# automata.net
KiCad netlist of a schematic drawn in EAGLE
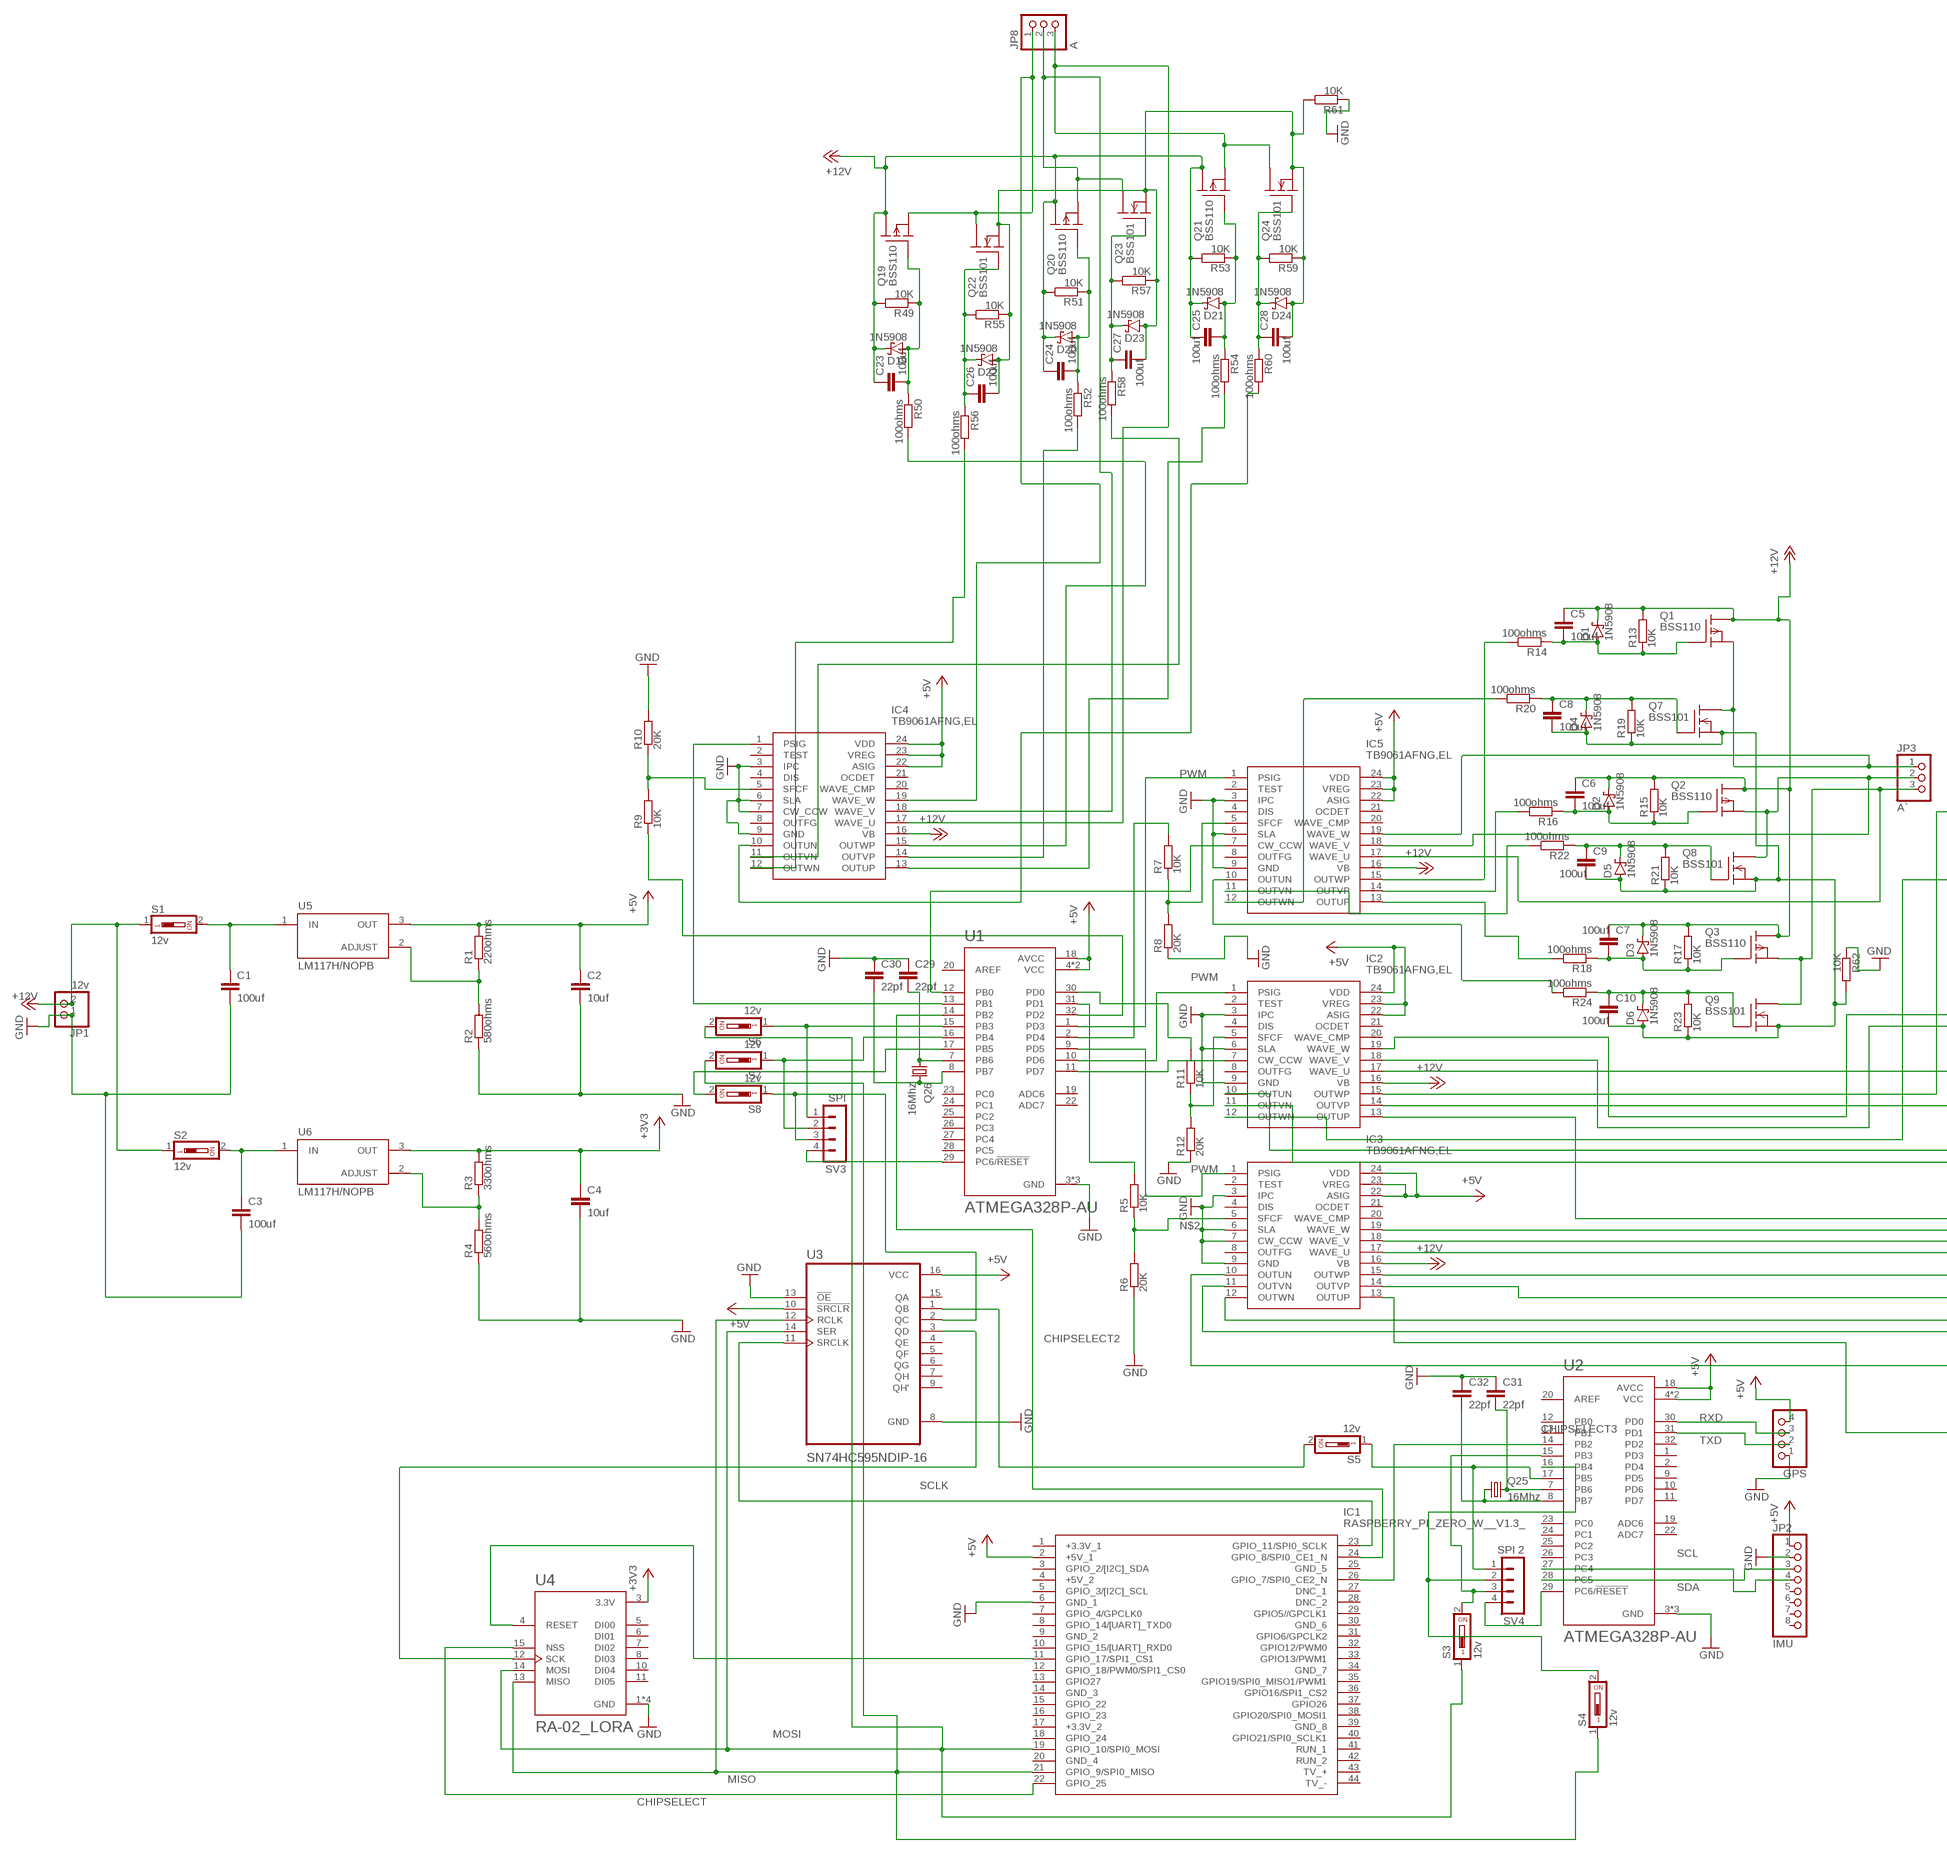
[diagram p0: schematic, sheet 1, part 1 of 2]
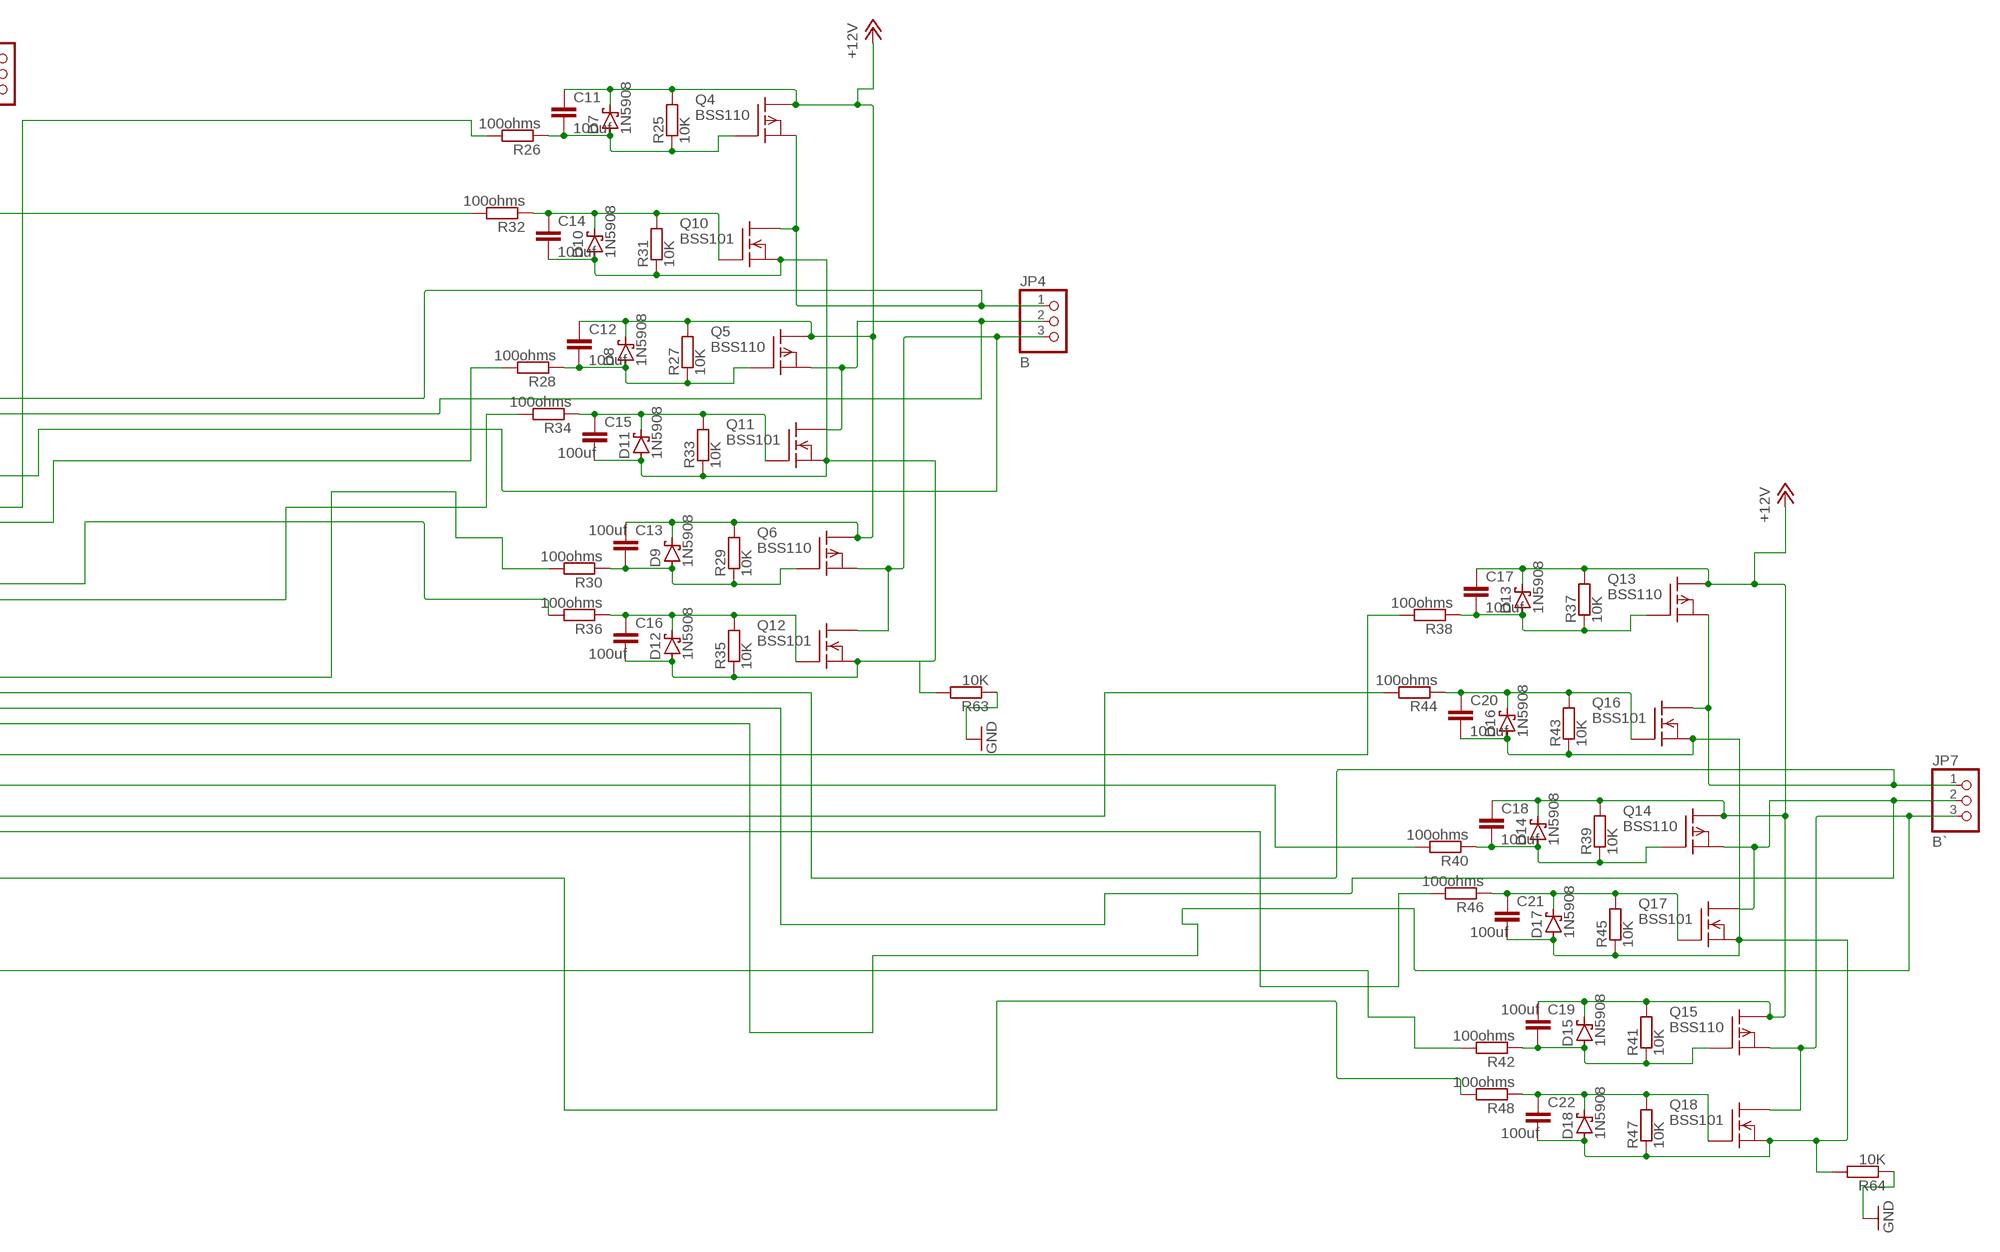
[diagram p1: schematic, sheet 1, part 2 of 2]

(export (version "E")
  (design (tool "Eeschema 10.0.6"))
  (components
    (comp (ref "C1")
      (value "100uf")
      (footprint "eagle-import:C0402K")
      (libsource (lib "eagle-import") (part "C-EUC0402K"))
    )
    (comp (ref "C2")
      (value "10uf")
      (footprint "eagle-import:C0402K")
      (libsource (lib "eagle-import") (part "C-EUC0402K"))
    )
    (comp (ref "C3")
      (value "100uf")
      (footprint "eagle-import:C0402K")
      (libsource (lib "eagle-import") (part "C-EUC0402K"))
    )
    (comp (ref "C4")
      (value "10uf")
      (footprint "eagle-import:C0402K")
      (libsource (lib "eagle-import") (part "C-EUC0402K"))
    )
    (comp (ref "C5")
      (value "100uf")
      (footprint "eagle-import:C0402K")
      (libsource (lib "eagle-import") (part "C-EUC0402K"))
    )
    (comp (ref "C6")
      (value "100uf")
      (footprint "eagle-import:C0402K")
      (libsource (lib "eagle-import") (part "C-EUC0402K"))
    )
    (comp (ref "C7")
      (value "100uf")
      (footprint "eagle-import:C0402K")
      (libsource (lib "eagle-import") (part "C-EUC0402K"))
    )
    (comp (ref "C8")
      (value "100uf")
      (footprint "eagle-import:C0402K")
      (libsource (lib "eagle-import") (part "C-EUC0402K"))
    )
    (comp (ref "C9")
      (value "100uf")
      (footprint "eagle-import:C0402K")
      (libsource (lib "eagle-import") (part "C-EUC0402K"))
    )
    (comp (ref "C10")
      (value "100uf")
      (footprint "eagle-import:C0402K")
      (libsource (lib "eagle-import") (part "C-EUC0402K"))
    )
    (comp (ref "C11")
      (value "100uf")
      (footprint "eagle-import:C0402K")
      (libsource (lib "eagle-import") (part "C-EUC0402K"))
    )
    (comp (ref "C12")
      (value "100uf")
      (footprint "eagle-import:C0402K")
      (libsource (lib "eagle-import") (part "C-EUC0402K"))
    )
    (comp (ref "C13")
      (value "100uf")
      (footprint "eagle-import:C0402K")
      (libsource (lib "eagle-import") (part "C-EUC0402K"))
    )
    (comp (ref "C14")
      (value "100uf")
      (footprint "eagle-import:C0402K")
      (libsource (lib "eagle-import") (part "C-EUC0402K"))
    )
    (comp (ref "C15")
      (value "100uf")
      (footprint "eagle-import:C0402K")
      (libsource (lib "eagle-import") (part "C-EUC0402K"))
    )
    (comp (ref "C16")
      (value "100uf")
      (footprint "eagle-import:C0402K")
      (libsource (lib "eagle-import") (part "C-EUC0402K"))
    )
    (comp (ref "C17")
      (value "100uf")
      (footprint "eagle-import:C0402K")
      (libsource (lib "eagle-import") (part "C-EUC0402K"))
    )
    (comp (ref "C18")
      (value "100uf")
      (footprint "eagle-import:C0402K")
      (libsource (lib "eagle-import") (part "C-EUC0402K"))
    )
    (comp (ref "C19")
      (value "100uf")
      (footprint "eagle-import:C0402K")
      (libsource (lib "eagle-import") (part "C-EUC0402K"))
    )
    (comp (ref "C20")
      (value "100uf")
      (footprint "eagle-import:C0402K")
      (libsource (lib "eagle-import") (part "C-EUC0402K"))
    )
    (comp (ref "C21")
      (value "100uf")
      (footprint "eagle-import:C0402K")
      (libsource (lib "eagle-import") (part "C-EUC0402K"))
    )
    (comp (ref "C22")
      (value "100uf")
      (footprint "eagle-import:C0402K")
      (libsource (lib "eagle-import") (part "C-EUC0402K"))
    )
    (comp (ref "C23")
      (value "100uf")
      (footprint "eagle-import:C0402K")
      (libsource (lib "eagle-import") (part "C-EUC0402K"))
    )
    (comp (ref "C24")
      (value "100uf")
      (footprint "eagle-import:C0402K")
      (libsource (lib "eagle-import") (part "C-EUC0402K"))
    )
    (comp (ref "C25")
      (value "100uf")
      (footprint "eagle-import:C0402K")
      (libsource (lib "eagle-import") (part "C-EUC0402K"))
    )
    (comp (ref "C26")
      (value "100uf")
      (footprint "eagle-import:C0402K")
      (libsource (lib "eagle-import") (part "C-EUC0402K"))
    )
    (comp (ref "C27")
      (value "100uf")
      (footprint "eagle-import:C0402K")
      (libsource (lib "eagle-import") (part "C-EUC0402K"))
    )
    (comp (ref "C28")
      (value "100uf")
      (footprint "eagle-import:C0402K")
      (libsource (lib "eagle-import") (part "C-EUC0402K"))
    )
    (comp (ref "C29")
      (value "22pf")
      (footprint "eagle-import:C0402K")
      (libsource (lib "eagle-import") (part "C-EUC0402K"))
    )
    (comp (ref "C30")
      (value "22pf")
      (footprint "eagle-import:C0402K")
      (libsource (lib "eagle-import") (part "C-EUC0402K"))
    )
    (comp (ref "C31")
      (value "22pf")
      (footprint "eagle-import:C0402K")
      (libsource (lib "eagle-import") (part "C-EUC0402K"))
    )
    (comp (ref "C32")
      (value "22pf")
      (footprint "eagle-import:C0402K")
      (libsource (lib "eagle-import") (part "C-EUC0402K"))
    )
    (comp (ref "D1")
      (value "1N5908")
      (footprint "eagle-import:C4111-15")
      (libsource (lib "eagle-import") (part "1N5908"))
    )
    (comp (ref "D2")
      (value "1N5908")
      (footprint "eagle-import:C4111-15")
      (libsource (lib "eagle-import") (part "1N5908"))
    )
    (comp (ref "D3")
      (value "1N5908")
      (footprint "eagle-import:C4111-15")
      (libsource (lib "eagle-import") (part "1N5908"))
    )
    (comp (ref "D4")
      (value "1N5908")
      (footprint "eagle-import:C4111-15")
      (libsource (lib "eagle-import") (part "1N5908"))
    )
    (comp (ref "D5")
      (value "1N5908")
      (footprint "eagle-import:C4111-15")
      (libsource (lib "eagle-import") (part "1N5908"))
    )
    (comp (ref "D6")
      (value "1N5908")
      (footprint "eagle-import:C4111-15")
      (libsource (lib "eagle-import") (part "1N5908"))
    )
    (comp (ref "D7")
      (value "1N5908")
      (footprint "eagle-import:C4111-15")
      (libsource (lib "eagle-import") (part "1N5908"))
    )
    (comp (ref "D8")
      (value "1N5908")
      (footprint "eagle-import:C4111-15")
      (libsource (lib "eagle-import") (part "1N5908"))
    )
    (comp (ref "D9")
      (value "1N5908")
      (footprint "eagle-import:C4111-15")
      (libsource (lib "eagle-import") (part "1N5908"))
    )
    (comp (ref "D10")
      (value "1N5908")
      (footprint "eagle-import:C4111-15")
      (libsource (lib "eagle-import") (part "1N5908"))
    )
    (comp (ref "D11")
      (value "1N5908")
      (footprint "eagle-import:C4111-15")
      (libsource (lib "eagle-import") (part "1N5908"))
    )
    (comp (ref "D12")
      (value "1N5908")
      (footprint "eagle-import:C4111-15")
      (libsource (lib "eagle-import") (part "1N5908"))
    )
    (comp (ref "D13")
      (value "1N5908")
      (footprint "eagle-import:C4111-15")
      (libsource (lib "eagle-import") (part "1N5908"))
    )
    (comp (ref "D14")
      (value "1N5908")
      (footprint "eagle-import:C4111-15")
      (libsource (lib "eagle-import") (part "1N5908"))
    )
    (comp (ref "D15")
      (value "1N5908")
      (footprint "eagle-import:C4111-15")
      (libsource (lib "eagle-import") (part "1N5908"))
    )
    (comp (ref "D16")
      (value "1N5908")
      (footprint "eagle-import:C4111-15")
      (libsource (lib "eagle-import") (part "1N5908"))
    )
    (comp (ref "D17")
      (value "1N5908")
      (footprint "eagle-import:C4111-15")
      (libsource (lib "eagle-import") (part "1N5908"))
    )
    (comp (ref "D18")
      (value "1N5908")
      (footprint "eagle-import:C4111-15")
      (libsource (lib "eagle-import") (part "1N5908"))
    )
    (comp (ref "D19")
      (value "1N5908")
      (footprint "eagle-import:C4111-15")
      (libsource (lib "eagle-import") (part "1N5908"))
    )
    (comp (ref "D20")
      (value "1N5908")
      (footprint "eagle-import:C4111-15")
      (libsource (lib "eagle-import") (part "1N5908"))
    )
    (comp (ref "D21")
      (value "1N5908")
      (footprint "eagle-import:C4111-15")
      (libsource (lib "eagle-import") (part "1N5908"))
    )
    (comp (ref "D22")
      (value "1N5908")
      (footprint "eagle-import:C4111-15")
      (libsource (lib "eagle-import") (part "1N5908"))
    )
    (comp (ref "D23")
      (value "1N5908")
      (footprint "eagle-import:C4111-15")
      (libsource (lib "eagle-import") (part "1N5908"))
    )
    (comp (ref "D24")
      (value "1N5908")
      (footprint "eagle-import:C4111-15")
      (libsource (lib "eagle-import") (part "1N5908"))
    )
    (comp (ref "GPS")
      (value "PINHD-1X4")
      (footprint "eagle-import:1X04")
      (libsource (lib "eagle-import") (part "PINHD-1X4"))
    )
    (comp (ref "IC1")
      (value "RASPBERRY_PI_ZERO_W__V1.3_")
      (footprint "eagle-import:RASPBERRYPIZEROWV13")
      (fields (field (name "MANUFACTURER_PART_NUMBER") "Raspberry Pi Zero W (v1.3)"))
      (libsource (lib "eagle-import") (part "RASPBERRY_PI_ZERO_W__V1.3_"))
    )
    (comp (ref "IC2")
      (value "TB9061AFNG,EL")
      (footprint "eagle-import:SOP65P760X160-24N")
      (fields (field (name "MOUSER_PART_NUMBER") "757-TB9061AFNG,EL"))
      (libsource (lib "eagle-import") (part "TB9061AFNG,EL"))
    )
    (comp (ref "IC3")
      (value "TB9061AFNG,EL")
      (footprint "eagle-import:SOP65P760X160-24N")
      (fields (field (name "MOUSER_PART_NUMBER") "757-TB9061AFNG,EL"))
      (libsource (lib "eagle-import") (part "TB9061AFNG,EL"))
    )
    (comp (ref "IC4")
      (value "TB9061AFNG,EL")
      (footprint "eagle-import:SOP65P760X160-24N")
      (fields (field (name "MOUSER_PART_NUMBER") "757-TB9061AFNG,EL"))
      (libsource (lib "eagle-import") (part "TB9061AFNG,EL"))
    )
    (comp (ref "IC5")
      (value "TB9061AFNG,EL")
      (footprint "eagle-import:SOP65P760X160-24N")
      (fields (field (name "MOUSER_PART_NUMBER") "757-TB9061AFNG,EL"))
      (libsource (lib "eagle-import") (part "TB9061AFNG,EL"))
    )
    (comp (ref "JP1")
      (value "12v")
      (footprint "eagle-import:1X02")
      (libsource (lib "eagle-import") (part "PINHD-1X2"))
    )
    (comp (ref "JP2")
      (value "IMU")
      (footprint "eagle-import:1X08")
      (libsource (lib "eagle-import") (part "PINHD-1X8"))
    )
    (comp (ref "JP3")
      (value "A`")
      (footprint "eagle-import:1X03")
      (libsource (lib "eagle-import") (part "PINHD-1X3"))
    )
    (comp (ref "JP4")
      (value "B")
      (footprint "eagle-import:1X03")
      (libsource (lib "eagle-import") (part "PINHD-1X3"))
    )
    (comp (ref "JP7")
      (value "B`")
      (footprint "eagle-import:1X03")
      (libsource (lib "eagle-import") (part "PINHD-1X3"))
    )
    (comp (ref "JP8")
      (value "A")
      (footprint "eagle-import:1X03")
      (libsource (lib "eagle-import") (part "PINHD-1X3"))
    )
    (comp (ref "Q1")
      (value "BSS110")
      (footprint "eagle-import:TO92")
      (libsource (lib "eagle-import") (part "BSS110"))
    )
    (comp (ref "Q2")
      (value "BSS110")
      (footprint "eagle-import:TO92")
      (libsource (lib "eagle-import") (part "BSS110"))
    )
    (comp (ref "Q3")
      (value "BSS110")
      (footprint "eagle-import:TO92")
      (libsource (lib "eagle-import") (part "BSS110"))
    )
    (comp (ref "Q4")
      (value "BSS110")
      (footprint "eagle-import:TO92")
      (libsource (lib "eagle-import") (part "BSS110"))
    )
    (comp (ref "Q5")
      (value "BSS110")
      (footprint "eagle-import:TO92")
      (libsource (lib "eagle-import") (part "BSS110"))
    )
    (comp (ref "Q6")
      (value "BSS110")
      (footprint "eagle-import:TO92")
      (libsource (lib "eagle-import") (part "BSS110"))
    )
    (comp (ref "Q7")
      (value "BSS101")
      (footprint "eagle-import:TO92")
      (libsource (lib "eagle-import") (part "BSS101"))
    )
    (comp (ref "Q8")
      (value "BSS101")
      (footprint "eagle-import:TO92")
      (libsource (lib "eagle-import") (part "BSS101"))
    )
    (comp (ref "Q9")
      (value "BSS101")
      (footprint "eagle-import:TO92")
      (libsource (lib "eagle-import") (part "BSS101"))
    )
    (comp (ref "Q10")
      (value "BSS101")
      (footprint "eagle-import:TO92")
      (libsource (lib "eagle-import") (part "BSS101"))
    )
    (comp (ref "Q11")
      (value "BSS101")
      (footprint "eagle-import:TO92")
      (libsource (lib "eagle-import") (part "BSS101"))
    )
    (comp (ref "Q12")
      (value "BSS101")
      (footprint "eagle-import:TO92")
      (libsource (lib "eagle-import") (part "BSS101"))
    )
    (comp (ref "Q13")
      (value "BSS110")
      (footprint "eagle-import:TO92")
      (libsource (lib "eagle-import") (part "BSS110"))
    )
    (comp (ref "Q14")
      (value "BSS110")
      (footprint "eagle-import:TO92")
      (libsource (lib "eagle-import") (part "BSS110"))
    )
    (comp (ref "Q15")
      (value "BSS110")
      (footprint "eagle-import:TO92")
      (libsource (lib "eagle-import") (part "BSS110"))
    )
    (comp (ref "Q16")
      (value "BSS101")
      (footprint "eagle-import:TO92")
      (libsource (lib "eagle-import") (part "BSS101"))
    )
    (comp (ref "Q17")
      (value "BSS101")
      (footprint "eagle-import:TO92")
      (libsource (lib "eagle-import") (part "BSS101"))
    )
    (comp (ref "Q18")
      (value "BSS101")
      (footprint "eagle-import:TO92")
      (libsource (lib "eagle-import") (part "BSS101"))
    )
    (comp (ref "Q19")
      (value "BSS110")
      (footprint "eagle-import:TO92")
      (libsource (lib "eagle-import") (part "BSS110"))
    )
    (comp (ref "Q20")
      (value "BSS110")
      (footprint "eagle-import:TO92")
      (libsource (lib "eagle-import") (part "BSS110"))
    )
    (comp (ref "Q21")
      (value "BSS110")
      (footprint "eagle-import:TO92")
      (libsource (lib "eagle-import") (part "BSS110"))
    )
    (comp (ref "Q22")
      (value "BSS101")
      (footprint "eagle-import:TO92")
      (libsource (lib "eagle-import") (part "BSS101"))
    )
    (comp (ref "Q23")
      (value "BSS101")
      (footprint "eagle-import:TO92")
      (libsource (lib "eagle-import") (part "BSS101"))
    )
    (comp (ref "Q24")
      (value "BSS101")
      (footprint "eagle-import:TO92")
      (libsource (lib "eagle-import") (part "BSS101"))
    )
    (comp (ref "Q25")
      (value "16Mhz")
      (footprint "eagle-import:HC49_S")
      (libsource (lib "eagle-import") (part "CRYSTALHC49S"))
    )
    (comp (ref "Q26")
      (value "16Mhz")
      (footprint "eagle-import:HC49_S")
      (libsource (lib "eagle-import") (part "CRYSTALHC49S"))
    )
    (comp (ref "R1")
      (value "220ohms")
      (footprint "eagle-import:SMK")
      (libsource (lib "eagle-import") (part "SMK"))
    )
    (comp (ref "R2")
      (value "580ohms")
      (footprint "eagle-import:SMK")
      (libsource (lib "eagle-import") (part "SMK"))
    )
    (comp (ref "R3")
      (value "330ohms")
      (footprint "eagle-import:SMK")
      (libsource (lib "eagle-import") (part "SMK"))
    )
    (comp (ref "R4")
      (value "560ohms")
      (footprint "eagle-import:SMK")
      (libsource (lib "eagle-import") (part "SMK"))
    )
    (comp (ref "R5")
      (value "10K")
      (footprint "eagle-import:SMK")
      (libsource (lib "eagle-import") (part "SMK"))
    )
    (comp (ref "R6")
      (value "20K")
      (footprint "eagle-import:SMK")
      (libsource (lib "eagle-import") (part "SMK"))
    )
    (comp (ref "R7")
      (value "10K")
      (footprint "eagle-import:SMK")
      (libsource (lib "eagle-import") (part "SMK"))
    )
    (comp (ref "R8")
      (value "20K")
      (footprint "eagle-import:SMK")
      (libsource (lib "eagle-import") (part "SMK"))
    )
    (comp (ref "R9")
      (value "10K")
      (footprint "eagle-import:SMK")
      (libsource (lib "eagle-import") (part "SMK"))
    )
    (comp (ref "R10")
      (value "20K")
      (footprint "eagle-import:SMK")
      (libsource (lib "eagle-import") (part "SMK"))
    )
    (comp (ref "R11")
      (value "10K")
      (footprint "eagle-import:SMK")
      (libsource (lib "eagle-import") (part "SMK"))
    )
    (comp (ref "R12")
      (value "20K")
      (footprint "eagle-import:SMK")
      (libsource (lib "eagle-import") (part "SMK"))
    )
    (comp (ref "R13")
      (value "10K")
      (footprint "eagle-import:SMK")
      (libsource (lib "eagle-import") (part "SMK"))
    )
    (comp (ref "R14")
      (value "100ohms")
      (footprint "eagle-import:SMK")
      (libsource (lib "eagle-import") (part "SMK"))
    )
    (comp (ref "R15")
      (value "10K")
      (footprint "eagle-import:SMK")
      (libsource (lib "eagle-import") (part "SMK"))
    )
    (comp (ref "R16")
      (value "100ohms")
      (footprint "eagle-import:SMK")
      (libsource (lib "eagle-import") (part "SMK"))
    )
    (comp (ref "R17")
      (value "10K")
      (footprint "eagle-import:SMK")
      (libsource (lib "eagle-import") (part "SMK"))
    )
    (comp (ref "R18")
      (value "100ohms")
      (footprint "eagle-import:SMK")
      (libsource (lib "eagle-import") (part "SMK"))
    )
    (comp (ref "R19")
      (value "10K")
      (footprint "eagle-import:SMK")
      (libsource (lib "eagle-import") (part "SMK"))
    )
    (comp (ref "R20")
      (value "100ohms")
      (footprint "eagle-import:SMK")
      (libsource (lib "eagle-import") (part "SMK"))
    )
    (comp (ref "R21")
      (value "10K")
      (footprint "eagle-import:SMK")
      (libsource (lib "eagle-import") (part "SMK"))
    )
    (comp (ref "R22")
      (value "100ohms")
      (footprint "eagle-import:SMK")
      (libsource (lib "eagle-import") (part "SMK"))
    )
    (comp (ref "R23")
      (value "10K")
      (footprint "eagle-import:SMK")
      (libsource (lib "eagle-import") (part "SMK"))
    )
    (comp (ref "R24")
      (value "100ohms")
      (footprint "eagle-import:SMK")
      (libsource (lib "eagle-import") (part "SMK"))
    )
    (comp (ref "R25")
      (value "10K")
      (footprint "eagle-import:SMK")
      (libsource (lib "eagle-import") (part "SMK"))
    )
    (comp (ref "R26")
      (value "100ohms")
      (footprint "eagle-import:SMK")
      (libsource (lib "eagle-import") (part "SMK"))
    )
    (comp (ref "R27")
      (value "10K")
      (footprint "eagle-import:SMK")
      (libsource (lib "eagle-import") (part "SMK"))
    )
    (comp (ref "R28")
      (value "100ohms")
      (footprint "eagle-import:SMK")
      (libsource (lib "eagle-import") (part "SMK"))
    )
    (comp (ref "R29")
      (value "10K")
      (footprint "eagle-import:SMK")
      (libsource (lib "eagle-import") (part "SMK"))
    )
    (comp (ref "R30")
      (value "100ohms")
      (footprint "eagle-import:SMK")
      (libsource (lib "eagle-import") (part "SMK"))
    )
    (comp (ref "R31")
      (value "10K")
      (footprint "eagle-import:SMK")
      (libsource (lib "eagle-import") (part "SMK"))
    )
    (comp (ref "R32")
      (value "100ohms")
      (footprint "eagle-import:SMK")
      (libsource (lib "eagle-import") (part "SMK"))
    )
    (comp (ref "R33")
      (value "10K")
      (footprint "eagle-import:SMK")
      (libsource (lib "eagle-import") (part "SMK"))
    )
    (comp (ref "R34")
      (value "100ohms")
      (footprint "eagle-import:SMK")
      (libsource (lib "eagle-import") (part "SMK"))
    )
    (comp (ref "R35")
      (value "10K")
      (footprint "eagle-import:SMK")
      (libsource (lib "eagle-import") (part "SMK"))
    )
    (comp (ref "R36")
      (value "100ohms")
      (footprint "eagle-import:SMK")
      (libsource (lib "eagle-import") (part "SMK"))
    )
    (comp (ref "R37")
      (value "10K")
      (footprint "eagle-import:SMK")
      (libsource (lib "eagle-import") (part "SMK"))
    )
    (comp (ref "R38")
      (value "100ohms")
      (footprint "eagle-import:SMK")
      (libsource (lib "eagle-import") (part "SMK"))
    )
    (comp (ref "R39")
      (value "10K")
      (footprint "eagle-import:SMK")
      (libsource (lib "eagle-import") (part "SMK"))
    )
    (comp (ref "R40")
      (value "100ohms")
      (footprint "eagle-import:SMK")
      (libsource (lib "eagle-import") (part "SMK"))
    )
    (comp (ref "R41")
      (value "10K")
      (footprint "eagle-import:SMK")
      (libsource (lib "eagle-import") (part "SMK"))
    )
    (comp (ref "R42")
      (value "100ohms")
      (footprint "eagle-import:SMK")
      (libsource (lib "eagle-import") (part "SMK"))
    )
    (comp (ref "R43")
      (value "10K")
      (footprint "eagle-import:SMK")
      (libsource (lib "eagle-import") (part "SMK"))
    )
    (comp (ref "R44")
      (value "100ohms")
      (footprint "eagle-import:SMK")
      (libsource (lib "eagle-import") (part "SMK"))
    )
    (comp (ref "R45")
      (value "10K")
      (footprint "eagle-import:SMK")
      (libsource (lib "eagle-import") (part "SMK"))
    )
    (comp (ref "R46")
      (value "100ohms")
      (footprint "eagle-import:SMK")
      (libsource (lib "eagle-import") (part "SMK"))
    )
    (comp (ref "R47")
      (value "10K")
      (footprint "eagle-import:SMK")
      (libsource (lib "eagle-import") (part "SMK"))
    )
    (comp (ref "R48")
      (value "100ohms")
      (footprint "eagle-import:SMK")
      (libsource (lib "eagle-import") (part "SMK"))
    )
    (comp (ref "R49")
      (value "10K")
      (footprint "eagle-import:SMK")
      (libsource (lib "eagle-import") (part "SMK"))
    )
    (comp (ref "R50")
      (value "100ohms")
      (footprint "eagle-import:SMK")
      (libsource (lib "eagle-import") (part "SMK"))
    )
    (comp (ref "R51")
      (value "10K")
      (footprint "eagle-import:SMK")
      (libsource (lib "eagle-import") (part "SMK"))
    )
    (comp (ref "R52")
      (value "100ohms")
      (footprint "eagle-import:SMK")
      (libsource (lib "eagle-import") (part "SMK"))
    )
    (comp (ref "R53")
      (value "10K")
      (footprint "eagle-import:SMK")
      (libsource (lib "eagle-import") (part "SMK"))
    )
    (comp (ref "R54")
      (value "100ohms")
      (footprint "eagle-import:SMK")
      (libsource (lib "eagle-import") (part "SMK"))
    )
    (comp (ref "R55")
      (value "10K")
      (footprint "eagle-import:SMK")
      (libsource (lib "eagle-import") (part "SMK"))
    )
    (comp (ref "R56")
      (value "100ohms")
      (footprint "eagle-import:SMK")
      (libsource (lib "eagle-import") (part "SMK"))
    )
    (comp (ref "R57")
      (value "10K")
      (footprint "eagle-import:SMK")
      (libsource (lib "eagle-import") (part "SMK"))
    )
    (comp (ref "R58")
      (value "100ohms")
      (footprint "eagle-import:SMK")
      (libsource (lib "eagle-import") (part "SMK"))
    )
    (comp (ref "R59")
      (value "10K")
      (footprint "eagle-import:SMK")
      (libsource (lib "eagle-import") (part "SMK"))
    )
    (comp (ref "R60")
      (value "100ohms")
      (footprint "eagle-import:SMK")
      (libsource (lib "eagle-import") (part "SMK"))
    )
    (comp (ref "R61")
      (value "10K")
      (footprint "eagle-import:SMK")
      (libsource (lib "eagle-import") (part "SMK"))
    )
    (comp (ref "R62")
      (value "10K")
      (footprint "eagle-import:SMK")
      (libsource (lib "eagle-import") (part "SMK"))
    )
    (comp (ref "R63")
      (value "10K")
      (footprint "eagle-import:SMK")
      (libsource (lib "eagle-import") (part "SMK"))
    )
    (comp (ref "R64")
      (value "10K")
      (footprint "eagle-import:SMK")
      (libsource (lib "eagle-import") (part "SMK"))
    )
    (comp (ref "S1")
      (value "12v")
      (footprint "eagle-import:DS-01")
      (libsource (lib "eagle-import") (part "DS01"))
    )
    (comp (ref "S2")
      (value "12v")
      (footprint "eagle-import:DS-01")
      (libsource (lib "eagle-import") (part "DS01"))
    )
    (comp (ref "S3")
      (value "12v")
      (footprint "eagle-import:DS-01")
      (libsource (lib "eagle-import") (part "DS01"))
    )
    (comp (ref "S4")
      (value "12v")
      (footprint "eagle-import:DS-01")
      (libsource (lib "eagle-import") (part "DS01"))
    )
    (comp (ref "S5")
      (value "12v")
      (footprint "eagle-import:DS-01")
      (libsource (lib "eagle-import") (part "DS01"))
    )
    (comp (ref "S6")
      (value "12v")
      (footprint "eagle-import:DS-01")
      (libsource (lib "eagle-import") (part "DS01"))
    )
    (comp (ref "S7")
      (value "12v")
      (footprint "eagle-import:DS-01")
      (libsource (lib "eagle-import") (part "DS01"))
    )
    (comp (ref "S8")
      (value "12v")
      (footprint "eagle-import:DS-01")
      (libsource (lib "eagle-import") (part "DS01"))
    )
    (comp (ref "SV3")
      (value "SPI")
      (footprint "eagle-import:MA04-1")
      (libsource (lib "eagle-import") (part "MA04-1"))
    )
    (comp (ref "SV4")
      (value "SPI 2")
      (footprint "eagle-import:MA04-1")
      (libsource (lib "eagle-import") (part "MA04-1"))
    )
    (comp (ref "U1")
      (value "ATMEGA328P-AU")
      (footprint "eagle-import:QFP80P900X900X120-32N")
      (fields (field (name "MF") "Microchip Technology"))
      (libsource (lib "eagle-import") (part "ATMEGA328P-AU"))
    )
    (comp (ref "U2")
      (value "ATMEGA328P-AU")
      (footprint "eagle-import:QFP80P900X900X120-32N")
      (fields (field (name "MF") "Microchip Technology"))
      (libsource (lib "eagle-import") (part "ATMEGA328P-AU"))
    )
    (comp (ref "U3")
      (value "SN74HC595NDIP-16")
      (footprint "eagle-import:DIP794W45P254L1969H508Q16")
      (fields (field (name "MF") "Texas Instruments") (field (name "MP") "SN74HC595N"))
      (libsource (lib "eagle-import") (part "SN74HC595NDIP-16"))
    )
    (comp (ref "U4")
      (value "RA-02_LORA")
      (footprint "eagle-import:MODULE_RA-02_LORA")
      (fields (field (name "MF") "AI-Thinker") (field (name "MP") "Ra-02 LoRa"))
      (libsource (lib "eagle-import") (part "RA-02_LORA"))
    )
    (comp (ref "U5")
      (value "LM117H/NOPB")
      (footprint "eagle-import:TO254P914H670-3")
      (fields (field (name "MF") "Texas Instruments"))
      (libsource (lib "eagle-import") (part "LM117H/NOPB"))
    )
    (comp (ref "U6")
      (value "LM117H/NOPB")
      (footprint "eagle-import:TO254P914H670-3")
      (fields (field (name "MF") "Texas Instruments"))
      (libsource (lib "eagle-import") (part "LM117H/NOPB"))
    )
  )
  (nets
    (net (code "1") (name "+3V3") (class "Default")
      (node (ref "C4") (pin "1") (pinfunction "1_1") (pintype "passive"))
      (node (ref "R3") (pin "1") (pinfunction "1_1") (pintype "passive"))
      (node (ref "U4") (pin "3") (pinfunction "3.3V_3") (pintype "power_in"))
      (node (ref "U6") (pin "3") (pinfunction "OUT_3") (pintype "output"))
    )
    (net (code "2") (name "+5V") (class "Default")
      (node (ref "C2") (pin "1") (pinfunction "1_1") (pintype "passive"))
      (node (ref "GPS") (pin "4") (pinfunction "4_4") (pintype "passive"))
      (node (ref "IC1") (pin "2") (pinfunction "+5V_1_2") (pintype "bidirectional"))
      (node (ref "IC2") (pin "22") (pinfunction "ASIG_22") (pintype "bidirectional"))
      (node (ref "IC2") (pin "23") (pinfunction "VREG_23") (pintype "bidirectional"))
      (node (ref "IC2") (pin "24") (pinfunction "VDD_24") (pintype "bidirectional"))
      (node (ref "IC3") (pin "22") (pinfunction "ASIG_22") (pintype "bidirectional"))
      (node (ref "IC3") (pin "23") (pinfunction "VREG_23") (pintype "bidirectional"))
      (node (ref "IC3") (pin "24") (pinfunction "VDD_24") (pintype "bidirectional"))
      (node (ref "IC4") (pin "22") (pinfunction "ASIG_22") (pintype "bidirectional"))
      (node (ref "IC4") (pin "23") (pinfunction "VREG_23") (pintype "bidirectional"))
      (node (ref "IC4") (pin "24") (pinfunction "VDD_24") (pintype "bidirectional"))
      (node (ref "IC5") (pin "22") (pinfunction "ASIG_22") (pintype "bidirectional"))
      (node (ref "IC5") (pin "23") (pinfunction "VREG_23") (pintype "bidirectional"))
      (node (ref "IC5") (pin "24") (pinfunction "VDD_24") (pintype "bidirectional"))
      (node (ref "JP2") (pin "1") (pinfunction "1_1") (pintype "passive"))
      (node (ref "R1") (pin "1") (pinfunction "1_1") (pintype "passive"))
      (node (ref "U1") (pin "18") (pinfunction "AVCC_18") (pintype "power_in"))
      (node (ref "U1") (pin "4") (pinfunction "VCC_4") (pintype "power_in"))
      (node (ref "U1") (pin "6") (pinfunction "VCC_6") (pintype "power_in"))
      (node (ref "U2") (pin "18") (pinfunction "AVCC_18") (pintype "power_in"))
      (node (ref "U2") (pin "4") (pinfunction "VCC_4") (pintype "power_in"))
      (node (ref "U2") (pin "6") (pinfunction "VCC_6") (pintype "power_in"))
      (node (ref "U3") (pin "10") (pinfunction "~{SRCLR}_10") (pintype "input"))
      (node (ref "U3") (pin "16") (pinfunction "VCC_16") (pintype "power_in"))
      (node (ref "U5") (pin "3") (pinfunction "OUT_3") (pintype "output"))
    )
    (net (code "3") (name "+12V") (class "Default")
      (node (ref "C11") (pin "1") (pinfunction "1_1") (pintype "passive"))
      (node (ref "C12") (pin "1") (pinfunction "1_1") (pintype "passive"))
      (node (ref "C13") (pin "1") (pinfunction "1_1") (pintype "passive"))
      (node (ref "C17") (pin "1") (pinfunction "1_1") (pintype "passive"))
      (node (ref "C18") (pin "1") (pinfunction "1_1") (pintype "passive"))
      (node (ref "C19") (pin "1") (pinfunction "1_1") (pintype "passive"))
      (node (ref "C23") (pin "1") (pinfunction "1_1") (pintype "passive"))
      (node (ref "C24") (pin "1") (pinfunction "1_1") (pintype "passive"))
      (node (ref "C25") (pin "1") (pinfunction "1_1") (pintype "passive"))
      (node (ref "C5") (pin "1") (pinfunction "1_1") (pintype "passive"))
      (node (ref "C6") (pin "1") (pinfunction "1_1") (pintype "passive"))
      (node (ref "C7") (pin "1") (pinfunction "1_1") (pintype "passive"))
      (node (ref "D1") (pin "C") (pinfunction "C_C") (pintype "passive"))
      (node (ref "D13") (pin "C") (pinfunction "C_C") (pintype "passive"))
      (node (ref "D14") (pin "C") (pinfunction "C_C") (pintype "passive"))
      (node (ref "D15") (pin "C") (pinfunction "C_C") (pintype "passive"))
      (node (ref "D19") (pin "C") (pinfunction "C_C") (pintype "passive"))
      (node (ref "D2") (pin "C") (pinfunction "C_C") (pintype "passive"))
      (node (ref "D20") (pin "C") (pinfunction "C_C") (pintype "passive"))
      (node (ref "D21") (pin "C") (pinfunction "C_C") (pintype "passive"))
      (node (ref "D3") (pin "C") (pinfunction "C_C") (pintype "passive"))
      (node (ref "D7") (pin "C") (pinfunction "C_C") (pintype "passive"))
      (node (ref "D8") (pin "C") (pinfunction "C_C") (pintype "passive"))
      (node (ref "D9") (pin "C") (pinfunction "C_C") (pintype "passive"))
      (node (ref "IC2") (pin "16") (pinfunction "VB_16") (pintype "bidirectional"))
      (node (ref "IC3") (pin "16") (pinfunction "VB_16") (pintype "bidirectional"))
      (node (ref "IC4") (pin "16") (pinfunction "VB_16") (pintype "bidirectional"))
      (node (ref "IC5") (pin "16") (pinfunction "VB_16") (pintype "bidirectional"))
      (node (ref "JP1") (pin "2") (pinfunction "2_2") (pintype "passive"))
      (node (ref "Q1") (pin "3") (pinfunction "D_3") (pintype "passive"))
      (node (ref "Q13") (pin "3") (pinfunction "D_3") (pintype "passive"))
      (node (ref "Q14") (pin "3") (pinfunction "D_3") (pintype "passive"))
      (node (ref "Q15") (pin "3") (pinfunction "D_3") (pintype "passive"))
      (node (ref "Q19") (pin "3") (pinfunction "D_3") (pintype "passive"))
      (node (ref "Q2") (pin "3") (pinfunction "D_3") (pintype "passive"))
      (node (ref "Q20") (pin "3") (pinfunction "D_3") (pintype "passive"))
      (node (ref "Q21") (pin "3") (pinfunction "D_3") (pintype "passive"))
      (node (ref "Q3") (pin "3") (pinfunction "D_3") (pintype "passive"))
      (node (ref "Q4") (pin "3") (pinfunction "D_3") (pintype "passive"))
      (node (ref "Q5") (pin "3") (pinfunction "D_3") (pintype "passive"))
      (node (ref "Q6") (pin "3") (pinfunction "D_3") (pintype "passive"))
      (node (ref "R13") (pin "1") (pinfunction "1_1") (pintype "passive"))
      (node (ref "R15") (pin "1") (pinfunction "1_1") (pintype "passive"))
      (node (ref "R17") (pin "1") (pinfunction "1_1") (pintype "passive"))
      (node (ref "R25") (pin "1") (pinfunction "1_1") (pintype "passive"))
      (node (ref "R27") (pin "1") (pinfunction "1_1") (pintype "passive"))
      (node (ref "R29") (pin "1") (pinfunction "1_1") (pintype "passive"))
      (node (ref "R37") (pin "1") (pinfunction "1_1") (pintype "passive"))
      (node (ref "R39") (pin "1") (pinfunction "1_1") (pintype "passive"))
      (node (ref "R41") (pin "1") (pinfunction "1_1") (pintype "passive"))
      (node (ref "R49") (pin "1") (pinfunction "1_1") (pintype "passive"))
      (node (ref "R51") (pin "1") (pinfunction "1_1") (pintype "passive"))
      (node (ref "R53") (pin "1") (pinfunction "1_1") (pintype "passive"))
      (node (ref "S1") (pin "1") (pinfunction "1_1") (pintype "passive"))
      (node (ref "S2") (pin "1") (pinfunction "1_1") (pintype "passive"))
    )
    (net (code "4") (name "/CHIPSELECT") (class "Default")
      (node (ref "IC1") (pin "22") (pinfunction "GPIO_25_22") (pintype "bidirectional"))
      (node (ref "U4") (pin "15") (pinfunction "NSS_15") (pintype "input"))
    )
    (net (code "5") (name "/CHIPSELECT2") (class "Default")
      (node (ref "IC1") (pin "24") (pinfunction "GPIO_8/SPI0_CE1_N_24") (pintype "bidirectional"))
      (node (ref "U1") (pin "14") (pinfunction "PB2_14") (pintype "bidirectional"))
    )
    (net (code "6") (name "/CHIPSELECT3") (class "Default")
      (node (ref "IC1") (pin "26") (pinfunction "GPIO_7/SPI0_CE2_N_26") (pintype "bidirectional"))
      (node (ref "U2") (pin "14") (pinfunction "PB2_14") (pintype "bidirectional"))
    )
    (net (code "7") (name "/MISO") (class "Default")
      (node (ref "IC1") (pin "21") (pinfunction "GPIO_9/SPI0_MISO_21") (pintype "bidirectional"))
      (node (ref "S4") (pin "1") (pinfunction "1_1") (pintype "passive"))
      (node (ref "S7") (pin "2") (pinfunction "2_2") (pintype "passive"))
      (node (ref "U3") (pin "12") (pinfunction "RCLK_12") (pintype "input"))
      (node (ref "U4") (pin "13") (pinfunction "MISO_13") (pintype "output"))
    )
    (net (code "8") (name "/MOSI") (class "Default")
      (node (ref "IC1") (pin "19") (pinfunction "GPIO_10/SPI0_MOSI_19") (pintype "bidirectional"))
      (node (ref "S3") (pin "1") (pinfunction "1_1") (pintype "passive"))
      (node (ref "S6") (pin "2") (pinfunction "2_2") (pintype "passive"))
      (node (ref "U3") (pin "14") (pinfunction "SER_14") (pintype "input"))
      (node (ref "U4") (pin "14") (pinfunction "MOSI_14") (pintype "input"))
    )
    (net (code "9") (name "/N$2") (class "Default")
      (node (ref "IC3") (pin "5") (pinfunction "SFCF_5") (pintype "bidirectional"))
      (node (ref "R5") (pin "2") (pinfunction "2_2") (pintype "passive"))
      (node (ref "R6") (pin "1") (pinfunction "1_1") (pintype "passive"))
    )
    (net (code "10") (name "/PWM") (class "Default")
      (node (ref "IC2") (pin "1") (pinfunction "PSIG_1") (pintype "bidirectional"))
      (node (ref "U1") (pin "10") (pinfunction "PD6_10") (pintype "bidirectional"))
    )
    (net (code "11") (name "/RXD") (class "Default")
      (node (ref "GPS") (pin "3") (pinfunction "3_3") (pintype "passive"))
      (node (ref "U2") (pin "30") (pinfunction "PD0_30") (pintype "bidirectional"))
    )
    (net (code "12") (name "/SCL") (class "Default")
      (node (ref "JP2") (pin "4") (pinfunction "4_4") (pintype "passive"))
      (node (ref "U2") (pin "27") (pinfunction "PC4_27") (pintype "bidirectional"))
    )
    (net (code "13") (name "/SCLK") (class "Default")
      (node (ref "IC1") (pin "23") (pinfunction "GPIO_11/SPI0_SCLK_23") (pintype "bidirectional"))
      (node (ref "U3") (pin "11") (pinfunction "SRCLK_11") (pintype "input"))
    )
    (net (code "14") (name "/SDA") (class "Default")
      (node (ref "JP2") (pin "3") (pinfunction "3_3") (pintype "passive"))
      (node (ref "U2") (pin "28") (pinfunction "PC5_28") (pintype "bidirectional"))
    )
    (net (code "15") (name "/TXD") (class "Default")
      (node (ref "GPS") (pin "2") (pinfunction "2_2") (pintype "passive"))
      (node (ref "U2") (pin "31") (pinfunction "PD1_31") (pintype "bidirectional"))
    )
    (net (code "16") (name "GND") (class "Default")
      (node (ref "C1") (pin "2") (pinfunction "2_2") (pintype "passive"))
      (node (ref "C2") (pin "2") (pinfunction "2_2") (pintype "passive"))
      (node (ref "C29") (pin "1") (pinfunction "1_1") (pintype "passive"))
      (node (ref "C3") (pin "2") (pinfunction "2_2") (pintype "passive"))
      (node (ref "C30") (pin "1") (pinfunction "1_1") (pintype "passive"))
      (node (ref "C31") (pin "1") (pinfunction "1_1") (pintype "passive"))
      (node (ref "C32") (pin "1") (pinfunction "1_1") (pintype "passive"))
      (node (ref "C4") (pin "2") (pinfunction "2_2") (pintype "passive"))
      (node (ref "GPS") (pin "1") (pinfunction "1_1") (pintype "passive"))
      (node (ref "IC1") (pin "6") (pinfunction "GND_1_6") (pintype "bidirectional"))
      (node (ref "IC2") (pin "3") (pinfunction "IPC_3") (pintype "bidirectional"))
      (node (ref "IC2") (pin "6") (pinfunction "SLA_6") (pintype "bidirectional"))
      (node (ref "IC2") (pin "9") (pinfunction "GND_9") (pintype "bidirectional"))
      (node (ref "IC3") (pin "3") (pinfunction "IPC_3") (pintype "bidirectional"))
      (node (ref "IC3") (pin "6") (pinfunction "SLA_6") (pintype "bidirectional"))
      (node (ref "IC3") (pin "7") (pinfunction "CW_CCW_7") (pintype "bidirectional"))
      (node (ref "IC3") (pin "9") (pinfunction "GND_9") (pintype "bidirectional"))
      (node (ref "IC4") (pin "3") (pinfunction "IPC_3") (pintype "bidirectional"))
      (node (ref "IC4") (pin "6") (pinfunction "SLA_6") (pintype "bidirectional"))
      (node (ref "IC4") (pin "7") (pinfunction "CW_CCW_7") (pintype "bidirectional"))
      (node (ref "IC4") (pin "9") (pinfunction "GND_9") (pintype "bidirectional"))
      (node (ref "IC5") (pin "3") (pinfunction "IPC_3") (pintype "bidirectional"))
      (node (ref "IC5") (pin "6") (pinfunction "SLA_6") (pintype "bidirectional"))
      (node (ref "IC5") (pin "9") (pinfunction "GND_9") (pintype "bidirectional"))
      (node (ref "JP1") (pin "1") (pinfunction "1_1") (pintype "passive"))
      (node (ref "JP2") (pin "2") (pinfunction "2_2") (pintype "passive"))
      (node (ref "R10") (pin "1") (pinfunction "1_1") (pintype "passive"))
      (node (ref "R12") (pin "2") (pinfunction "2_2") (pintype "passive"))
      (node (ref "R2") (pin "2") (pinfunction "2_2") (pintype "passive"))
      (node (ref "R4") (pin "2") (pinfunction "2_2") (pintype "passive"))
      (node (ref "R6") (pin "2") (pinfunction "2_2") (pintype "passive"))
      (node (ref "R61") (pin "2") (pinfunction "2_2") (pintype "passive"))
      (node (ref "R62") (pin "2") (pinfunction "2_2") (pintype "passive"))
      (node (ref "R63") (pin "2") (pinfunction "2_2") (pintype "passive"))
      (node (ref "R64") (pin "2") (pinfunction "2_2") (pintype "passive"))
      (node (ref "R8") (pin "2") (pinfunction "2_2") (pintype "passive"))
      (node (ref "U1") (pin "21") (pinfunction "GND_21") (pintype "power_in"))
      (node (ref "U1") (pin "3") (pinfunction "GND_3") (pintype "power_in"))
      (node (ref "U1") (pin "5") (pinfunction "GND_5") (pintype "power_in"))
      (node (ref "U2") (pin "21") (pinfunction "GND_21") (pintype "power_in"))
      (node (ref "U2") (pin "3") (pinfunction "GND_3") (pintype "power_in"))
      (node (ref "U2") (pin "5") (pinfunction "GND_5") (pintype "power_in"))
      (node (ref "U3") (pin "13") (pinfunction "~{OE}_13") (pintype "input"))
      (node (ref "U3") (pin "8") (pinfunction "GND_8") (pintype "power_in"))
      (node (ref "U4") (pin "1") (pinfunction "GND_1") (pintype "power_in"))
      (node (ref "U4") (pin "16") (pinfunction "GND_16") (pintype "power_in"))
      (node (ref "U4") (pin "2") (pinfunction "GND_2") (pintype "power_in"))
      (node (ref "U4") (pin "9") (pinfunction "GND_9") (pintype "power_in"))
    )
    (net (code "17") (name "Net-(IC1-GPIO_17{slash}SPI1_CS1)") (class "Default")
      (node (ref "IC1") (pin "11") (pinfunction "GPIO_17/SPI1_CS1_11") (pintype "bidirectional"))
      (node (ref "U4") (pin "4") (pinfunction "RESET_4") (pintype "input"))
    )
    (net (code "18") (name "Net-(IC2-CW_CCW)") (class "Default")
      (node (ref "IC2") (pin "7") (pinfunction "CW_CCW_7") (pintype "bidirectional"))
      (node (ref "U1") (pin "11") (pinfunction "PD7_11") (pintype "bidirectional"))
    )
    (net (code "19") (name "Net-(IC2-OUTUN)") (class "Default")
      (node (ref "IC2") (pin "10") (pinfunction "OUTUN_10") (pintype "bidirectional"))
      (node (ref "R36") (pin "1") (pinfunction "1_1") (pintype "passive"))
    )
    (net (code "20") (name "Net-(IC2-OUTUP)") (class "Default")
      (node (ref "IC2") (pin "13") (pinfunction "OUTUP_13") (pintype "bidirectional"))
      (node (ref "R30") (pin "1") (pinfunction "1_1") (pintype "passive"))
    )
    (net (code "21") (name "Net-(IC2-OUTVN)") (class "Default")
      (node (ref "IC2") (pin "11") (pinfunction "OUTVN_11") (pintype "bidirectional"))
      (node (ref "R34") (pin "1") (pinfunction "1_1") (pintype "passive"))
    )
    (net (code "22") (name "Net-(IC2-OUTVP)") (class "Default")
      (node (ref "IC2") (pin "14") (pinfunction "OUTVP_14") (pintype "bidirectional"))
      (node (ref "R28") (pin "1") (pinfunction "1_1") (pintype "passive"))
    )
    (net (code "23") (name "Net-(IC2-OUTWN)") (class "Default")
      (node (ref "IC2") (pin "12") (pinfunction "OUTWN_12") (pintype "bidirectional"))
      (node (ref "R32") (pin "1") (pinfunction "1_1") (pintype "passive"))
    )
    (net (code "24") (name "Net-(IC2-OUTWP)") (class "Default")
      (node (ref "IC2") (pin "15") (pinfunction "OUTWP_15") (pintype "bidirectional"))
      (node (ref "R26") (pin "1") (pinfunction "1_1") (pintype "passive"))
    )
    (net (code "25") (name "Net-(IC2-SFCF)") (class "Default")
      (node (ref "IC2") (pin "5") (pinfunction "SFCF_5") (pintype "bidirectional"))
      (node (ref "R11") (pin "2") (pinfunction "2_2") (pintype "passive"))
      (node (ref "R12") (pin "1") (pinfunction "1_1") (pintype "passive"))
    )
    (net (code "26") (name "Net-(IC2-WAVE_U)") (class "Default")
      (node (ref "IC2") (pin "17") (pinfunction "WAVE_U_17") (pintype "bidirectional"))
      (node (ref "JP4") (pin "3") (pinfunction "3_3") (pintype "passive"))
      (node (ref "Q12") (pin "3") (pinfunction "D_3") (pintype "passive"))
      (node (ref "Q6") (pin "1") (pinfunction "S_1") (pintype "passive"))
    )
    (net (code "27") (name "Net-(IC2-WAVE_V)") (class "Default")
      (node (ref "IC2") (pin "18") (pinfunction "WAVE_V_18") (pintype "bidirectional"))
      (node (ref "JP4") (pin "2") (pinfunction "2_2") (pintype "passive"))
      (node (ref "Q11") (pin "3") (pinfunction "D_3") (pintype "passive"))
      (node (ref "Q5") (pin "1") (pinfunction "S_1") (pintype "passive"))
    )
    (net (code "28") (name "Net-(IC2-WAVE_W)") (class "Default")
      (node (ref "IC2") (pin "19") (pinfunction "WAVE_W_19") (pintype "bidirectional"))
      (node (ref "JP4") (pin "1") (pinfunction "1_1") (pintype "passive"))
      (node (ref "Q10") (pin "3") (pinfunction "D_3") (pintype "passive"))
      (node (ref "Q4") (pin "1") (pinfunction "S_1") (pintype "passive"))
    )
    (net (code "29") (name "Net-(IC3-OUTUN)") (class "Default")
      (node (ref "IC3") (pin "10") (pinfunction "OUTUN_10") (pintype "bidirectional"))
      (node (ref "R48") (pin "1") (pinfunction "1_1") (pintype "passive"))
    )
    (net (code "30") (name "Net-(IC3-OUTUP)") (class "Default")
      (node (ref "IC3") (pin "13") (pinfunction "OUTUP_13") (pintype "bidirectional"))
      (node (ref "R42") (pin "1") (pinfunction "1_1") (pintype "passive"))
    )
    (net (code "31") (name "Net-(IC3-OUTVN)") (class "Default")
      (node (ref "IC3") (pin "11") (pinfunction "OUTVN_11") (pintype "bidirectional"))
      (node (ref "R46") (pin "1") (pinfunction "1_1") (pintype "passive"))
    )
    (net (code "32") (name "Net-(IC3-OUTVP)") (class "Default")
      (node (ref "IC3") (pin "14") (pinfunction "OUTVP_14") (pintype "bidirectional"))
      (node (ref "R40") (pin "1") (pinfunction "1_1") (pintype "passive"))
    )
    (net (code "33") (name "Net-(IC3-OUTWN)") (class "Default")
      (node (ref "IC3") (pin "12") (pinfunction "OUTWN_12") (pintype "bidirectional"))
      (node (ref "R44") (pin "1") (pinfunction "1_1") (pintype "passive"))
    )
    (net (code "34") (name "Net-(IC3-OUTWP)") (class "Default")
      (node (ref "IC3") (pin "15") (pinfunction "OUTWP_15") (pintype "bidirectional"))
      (node (ref "R38") (pin "1") (pinfunction "1_1") (pintype "passive"))
    )
    (net (code "35") (name "Net-(IC3-PSIG)") (class "Default")
      (node (ref "IC3") (pin "1") (pinfunction "PSIG_1") (pintype "bidirectional"))
      (node (ref "U1") (pin "9") (pinfunction "PD5_9") (pintype "bidirectional"))
    )
    (net (code "36") (name "Net-(IC3-WAVE_U)") (class "Default")
      (node (ref "IC3") (pin "17") (pinfunction "WAVE_U_17") (pintype "bidirectional"))
      (node (ref "JP7") (pin "3") (pinfunction "3_3") (pintype "passive"))
      (node (ref "Q15") (pin "1") (pinfunction "S_1") (pintype "passive"))
      (node (ref "Q18") (pin "3") (pinfunction "D_3") (pintype "passive"))
    )
    (net (code "37") (name "Net-(IC3-WAVE_V)") (class "Default")
      (node (ref "IC3") (pin "18") (pinfunction "WAVE_V_18") (pintype "bidirectional"))
      (node (ref "JP7") (pin "2") (pinfunction "2_2") (pintype "passive"))
      (node (ref "Q14") (pin "1") (pinfunction "S_1") (pintype "passive"))
      (node (ref "Q17") (pin "3") (pinfunction "D_3") (pintype "passive"))
    )
    (net (code "38") (name "Net-(IC3-WAVE_W)") (class "Default")
      (node (ref "IC3") (pin "19") (pinfunction "WAVE_W_19") (pintype "bidirectional"))
      (node (ref "JP7") (pin "1") (pinfunction "1_1") (pintype "passive"))
      (node (ref "Q13") (pin "1") (pinfunction "S_1") (pintype "passive"))
      (node (ref "Q16") (pin "3") (pinfunction "D_3") (pintype "passive"))
    )
    (net (code "39") (name "Net-(IC4-OUTUN)") (class "Default")
      (node (ref "IC4") (pin "10") (pinfunction "OUTUN_10") (pintype "bidirectional"))
      (node (ref "R60") (pin "1") (pinfunction "1_1") (pintype "passive"))
    )
    (net (code "40") (name "Net-(IC4-OUTUP)") (class "Default")
      (node (ref "IC4") (pin "13") (pinfunction "OUTUP_13") (pintype "bidirectional"))
      (node (ref "R54") (pin "1") (pinfunction "1_1") (pintype "passive"))
    )
    (net (code "41") (name "Net-(IC4-OUTVN)") (class "Default")
      (node (ref "IC4") (pin "11") (pinfunction "OUTVN_11") (pintype "bidirectional"))
      (node (ref "R58") (pin "1") (pinfunction "1_1") (pintype "passive"))
    )
    (net (code "42") (name "Net-(IC4-OUTVP)") (class "Default")
      (node (ref "IC4") (pin "14") (pinfunction "OUTVP_14") (pintype "bidirectional"))
      (node (ref "R52") (pin "1") (pinfunction "1_1") (pintype "passive"))
    )
    (net (code "43") (name "Net-(IC4-OUTWN)") (class "Default")
      (node (ref "IC4") (pin "12") (pinfunction "OUTWN_12") (pintype "bidirectional"))
      (node (ref "R56") (pin "1") (pinfunction "1_1") (pintype "passive"))
    )
    (net (code "44") (name "Net-(IC4-OUTWP)") (class "Default")
      (node (ref "IC4") (pin "15") (pinfunction "OUTWP_15") (pintype "bidirectional"))
      (node (ref "R50") (pin "1") (pinfunction "1_1") (pintype "passive"))
    )
    (net (code "45") (name "Net-(IC4-PSIG)") (class "Default")
      (node (ref "IC4") (pin "1") (pinfunction "PSIG_1") (pintype "bidirectional"))
      (node (ref "U1") (pin "13") (pinfunction "PB1_13") (pintype "bidirectional"))
    )
    (net (code "46") (name "Net-(IC4-SFCF)") (class "Default")
      (node (ref "IC4") (pin "5") (pinfunction "SFCF_5") (pintype "bidirectional"))
      (node (ref "R10") (pin "2") (pinfunction "2_2") (pintype "passive"))
      (node (ref "R9") (pin "1") (pinfunction "1_1") (pintype "passive"))
    )
    (net (code "47") (name "Net-(IC4-WAVE_U)") (class "Default")
      (node (ref "IC4") (pin "17") (pinfunction "WAVE_U_17") (pintype "bidirectional"))
      (node (ref "JP8") (pin "3") (pinfunction "3_3") (pintype "passive"))
      (node (ref "Q21") (pin "1") (pinfunction "S_1") (pintype "passive"))
      (node (ref "Q24") (pin "3") (pinfunction "D_3") (pintype "passive"))
    )
    (net (code "48") (name "Net-(IC4-WAVE_V)") (class "Default")
      (node (ref "IC4") (pin "18") (pinfunction "WAVE_V_18") (pintype "bidirectional"))
      (node (ref "JP8") (pin "2") (pinfunction "2_2") (pintype "passive"))
      (node (ref "Q20") (pin "1") (pinfunction "S_1") (pintype "passive"))
      (node (ref "Q23") (pin "3") (pinfunction "D_3") (pintype "passive"))
    )
    (net (code "49") (name "Net-(IC4-WAVE_W)") (class "Default")
      (node (ref "IC4") (pin "19") (pinfunction "WAVE_W_19") (pintype "bidirectional"))
      (node (ref "JP8") (pin "1") (pinfunction "1_1") (pintype "passive"))
      (node (ref "Q19") (pin "1") (pinfunction "S_1") (pintype "passive"))
      (node (ref "Q22") (pin "3") (pinfunction "D_3") (pintype "passive"))
    )
    (net (code "50") (name "Net-(IC5-CW_CCW)") (class "Default")
      (node (ref "IC5") (pin "7") (pinfunction "CW_CCW_7") (pintype "bidirectional"))
      (node (ref "U1") (pin "12") (pinfunction "PB0_12") (pintype "bidirectional"))
    )
    (net (code "51") (name "Net-(IC5-OUTUN)") (class "Default")
      (node (ref "IC5") (pin "10") (pinfunction "OUTUN_10") (pintype "bidirectional"))
      (node (ref "R24") (pin "1") (pinfunction "1_1") (pintype "passive"))
    )
    (net (code "52") (name "Net-(IC5-OUTUP)") (class "Default")
      (node (ref "IC5") (pin "13") (pinfunction "OUTUP_13") (pintype "bidirectional"))
      (node (ref "R18") (pin "1") (pinfunction "1_1") (pintype "passive"))
    )
    (net (code "53") (name "Net-(IC5-OUTVN)") (class "Default")
      (node (ref "IC5") (pin "11") (pinfunction "OUTVN_11") (pintype "bidirectional"))
      (node (ref "R22") (pin "1") (pinfunction "1_1") (pintype "passive"))
    )
    (net (code "54") (name "Net-(IC5-OUTVP)") (class "Default")
      (node (ref "IC5") (pin "14") (pinfunction "OUTVP_14") (pintype "bidirectional"))
      (node (ref "R16") (pin "1") (pinfunction "1_1") (pintype "passive"))
    )
    (net (code "55") (name "Net-(IC5-OUTWN)") (class "Default")
      (node (ref "IC5") (pin "12") (pinfunction "OUTWN_12") (pintype "bidirectional"))
      (node (ref "R20") (pin "1") (pinfunction "1_1") (pintype "passive"))
    )
    (net (code "56") (name "Net-(IC5-OUTWP)") (class "Default")
      (node (ref "IC5") (pin "15") (pinfunction "OUTWP_15") (pintype "bidirectional"))
      (node (ref "R14") (pin "1") (pinfunction "1_1") (pintype "passive"))
    )
    (net (code "57") (name "Net-(IC5-PSIG)") (class "Default")
      (node (ref "IC5") (pin "1") (pinfunction "PSIG_1") (pintype "bidirectional"))
      (node (ref "U1") (pin "1") (pinfunction "PD3_1") (pintype "bidirectional"))
    )
    (net (code "58") (name "Net-(IC5-SFCF)") (class "Default")
      (node (ref "IC5") (pin "5") (pinfunction "SFCF_5") (pintype "bidirectional"))
      (node (ref "R7") (pin "2") (pinfunction "2_2") (pintype "passive"))
      (node (ref "R8") (pin "1") (pinfunction "1_1") (pintype "passive"))
    )
    (net (code "59") (name "Net-(IC5-WAVE_U)") (class "Default")
      (node (ref "IC5") (pin "17") (pinfunction "WAVE_U_17") (pintype "bidirectional"))
      (node (ref "JP3") (pin "3") (pinfunction "3_3") (pintype "passive"))
      (node (ref "Q3") (pin "1") (pinfunction "S_1") (pintype "passive"))
      (node (ref "Q9") (pin "3") (pinfunction "D_3") (pintype "passive"))
    )
    (net (code "60") (name "Net-(IC5-WAVE_V)") (class "Default")
      (node (ref "IC5") (pin "18") (pinfunction "WAVE_V_18") (pintype "bidirectional"))
      (node (ref "JP3") (pin "2") (pinfunction "2_2") (pintype "passive"))
      (node (ref "Q2") (pin "1") (pinfunction "S_1") (pintype "passive"))
      (node (ref "Q8") (pin "3") (pinfunction "D_3") (pintype "passive"))
    )
    (net (code "61") (name "Net-(IC5-WAVE_W)") (class "Default")
      (node (ref "IC5") (pin "19") (pinfunction "WAVE_W_19") (pintype "bidirectional"))
      (node (ref "JP3") (pin "1") (pinfunction "1_1") (pintype "passive"))
      (node (ref "Q1") (pin "1") (pinfunction "S_1") (pintype "passive"))
      (node (ref "Q7") (pin "3") (pinfunction "D_3") (pintype "passive"))
    )
    (net (code "62") (name "Net-(Q1-G)") (class "Default")
      (node (ref "C5") (pin "2") (pinfunction "2_2") (pintype "passive"))
      (node (ref "D1") (pin "A") (pinfunction "A_A") (pintype "passive"))
      (node (ref "Q1") (pin "2") (pinfunction "G_2") (pintype "passive"))
      (node (ref "R13") (pin "2") (pinfunction "2_2") (pintype "passive"))
      (node (ref "R14") (pin "2") (pinfunction "2_2") (pintype "passive"))
    )
    (net (code "63") (name "Net-(Q2-G)") (class "Default")
      (node (ref "C6") (pin "2") (pinfunction "2_2") (pintype "passive"))
      (node (ref "D2") (pin "A") (pinfunction "A_A") (pintype "passive"))
      (node (ref "Q2") (pin "2") (pinfunction "G_2") (pintype "passive"))
      (node (ref "R15") (pin "2") (pinfunction "2_2") (pintype "passive"))
      (node (ref "R16") (pin "2") (pinfunction "2_2") (pintype "passive"))
    )
    (net (code "64") (name "Net-(Q3-G)") (class "Default")
      (node (ref "C7") (pin "2") (pinfunction "2_2") (pintype "passive"))
      (node (ref "D3") (pin "A") (pinfunction "A_A") (pintype "passive"))
      (node (ref "Q3") (pin "2") (pinfunction "G_2") (pintype "passive"))
      (node (ref "R17") (pin "2") (pinfunction "2_2") (pintype "passive"))
      (node (ref "R18") (pin "2") (pinfunction "2_2") (pintype "passive"))
    )
    (net (code "65") (name "Net-(Q4-G)") (class "Default")
      (node (ref "C11") (pin "2") (pinfunction "2_2") (pintype "passive"))
      (node (ref "D7") (pin "A") (pinfunction "A_A") (pintype "passive"))
      (node (ref "Q4") (pin "2") (pinfunction "G_2") (pintype "passive"))
      (node (ref "R25") (pin "2") (pinfunction "2_2") (pintype "passive"))
      (node (ref "R26") (pin "2") (pinfunction "2_2") (pintype "passive"))
    )
    (net (code "66") (name "Net-(Q5-G)") (class "Default")
      (node (ref "C12") (pin "2") (pinfunction "2_2") (pintype "passive"))
      (node (ref "D8") (pin "A") (pinfunction "A_A") (pintype "passive"))
      (node (ref "Q5") (pin "2") (pinfunction "G_2") (pintype "passive"))
      (node (ref "R27") (pin "2") (pinfunction "2_2") (pintype "passive"))
      (node (ref "R28") (pin "2") (pinfunction "2_2") (pintype "passive"))
    )
    (net (code "67") (name "Net-(Q6-G)") (class "Default")
      (node (ref "C13") (pin "2") (pinfunction "2_2") (pintype "passive"))
      (node (ref "D9") (pin "A") (pinfunction "A_A") (pintype "passive"))
      (node (ref "Q6") (pin "2") (pinfunction "G_2") (pintype "passive"))
      (node (ref "R29") (pin "2") (pinfunction "2_2") (pintype "passive"))
      (node (ref "R30") (pin "2") (pinfunction "2_2") (pintype "passive"))
    )
    (net (code "68") (name "Net-(Q7-G)") (class "Default")
      (node (ref "C8") (pin "1") (pinfunction "1_1") (pintype "passive"))
      (node (ref "D4") (pin "C") (pinfunction "C_C") (pintype "passive"))
      (node (ref "Q7") (pin "2") (pinfunction "G_2") (pintype "passive"))
      (node (ref "R19") (pin "1") (pinfunction "1_1") (pintype "passive"))
      (node (ref "R20") (pin "2") (pinfunction "2_2") (pintype "passive"))
    )
    (net (code "69") (name "Net-(Q7-S)") (class "Default")
      (node (ref "C10") (pin "2") (pinfunction "2_2") (pintype "passive"))
      (node (ref "C8") (pin "2") (pinfunction "2_2") (pintype "passive"))
      (node (ref "C9") (pin "2") (pinfunction "2_2") (pintype "passive"))
      (node (ref "D4") (pin "A") (pinfunction "A_A") (pintype "passive"))
      (node (ref "D5") (pin "A") (pinfunction "A_A") (pintype "passive"))
      (node (ref "D6") (pin "A") (pinfunction "A_A") (pintype "passive"))
      (node (ref "Q7") (pin "1") (pinfunction "S_1") (pintype "passive"))
      (node (ref "Q8") (pin "1") (pinfunction "S_1") (pintype "passive"))
      (node (ref "Q9") (pin "1") (pinfunction "S_1") (pintype "passive"))
      (node (ref "R19") (pin "2") (pinfunction "2_2") (pintype "passive"))
      (node (ref "R21") (pin "2") (pinfunction "2_2") (pintype "passive"))
      (node (ref "R23") (pin "2") (pinfunction "2_2") (pintype "passive"))
      (node (ref "R62") (pin "1") (pinfunction "1_1") (pintype "passive"))
    )
    (net (code "70") (name "Net-(Q8-G)") (class "Default")
      (node (ref "C9") (pin "1") (pinfunction "1_1") (pintype "passive"))
      (node (ref "D5") (pin "C") (pinfunction "C_C") (pintype "passive"))
      (node (ref "Q8") (pin "2") (pinfunction "G_2") (pintype "passive"))
      (node (ref "R21") (pin "1") (pinfunction "1_1") (pintype "passive"))
      (node (ref "R22") (pin "2") (pinfunction "2_2") (pintype "passive"))
    )
    (net (code "71") (name "Net-(Q9-G)") (class "Default")
      (node (ref "C10") (pin "1") (pinfunction "1_1") (pintype "passive"))
      (node (ref "D6") (pin "C") (pinfunction "C_C") (pintype "passive"))
      (node (ref "Q9") (pin "2") (pinfunction "G_2") (pintype "passive"))
      (node (ref "R23") (pin "1") (pinfunction "1_1") (pintype "passive"))
      (node (ref "R24") (pin "2") (pinfunction "2_2") (pintype "passive"))
    )
    (net (code "72") (name "Net-(Q10-G)") (class "Default")
      (node (ref "C14") (pin "1") (pinfunction "1_1") (pintype "passive"))
      (node (ref "D10") (pin "C") (pinfunction "C_C") (pintype "passive"))
      (node (ref "Q10") (pin "2") (pinfunction "G_2") (pintype "passive"))
      (node (ref "R31") (pin "1") (pinfunction "1_1") (pintype "passive"))
      (node (ref "R32") (pin "2") (pinfunction "2_2") (pintype "passive"))
    )
    (net (code "73") (name "Net-(Q10-S)") (class "Default")
      (node (ref "C14") (pin "2") (pinfunction "2_2") (pintype "passive"))
      (node (ref "C15") (pin "2") (pinfunction "2_2") (pintype "passive"))
      (node (ref "C16") (pin "2") (pinfunction "2_2") (pintype "passive"))
      (node (ref "D10") (pin "A") (pinfunction "A_A") (pintype "passive"))
      (node (ref "D11") (pin "A") (pinfunction "A_A") (pintype "passive"))
      (node (ref "D12") (pin "A") (pinfunction "A_A") (pintype "passive"))
      (node (ref "Q10") (pin "1") (pinfunction "S_1") (pintype "passive"))
      (node (ref "Q11") (pin "1") (pinfunction "S_1") (pintype "passive"))
      (node (ref "Q12") (pin "1") (pinfunction "S_1") (pintype "passive"))
      (node (ref "R31") (pin "2") (pinfunction "2_2") (pintype "passive"))
      (node (ref "R33") (pin "2") (pinfunction "2_2") (pintype "passive"))
      (node (ref "R35") (pin "2") (pinfunction "2_2") (pintype "passive"))
      (node (ref "R63") (pin "1") (pinfunction "1_1") (pintype "passive"))
    )
    (net (code "74") (name "Net-(Q11-G)") (class "Default")
      (node (ref "C15") (pin "1") (pinfunction "1_1") (pintype "passive"))
      (node (ref "D11") (pin "C") (pinfunction "C_C") (pintype "passive"))
      (node (ref "Q11") (pin "2") (pinfunction "G_2") (pintype "passive"))
      (node (ref "R33") (pin "1") (pinfunction "1_1") (pintype "passive"))
      (node (ref "R34") (pin "2") (pinfunction "2_2") (pintype "passive"))
    )
    (net (code "75") (name "Net-(Q12-G)") (class "Default")
      (node (ref "C16") (pin "1") (pinfunction "1_1") (pintype "passive"))
      (node (ref "D12") (pin "C") (pinfunction "C_C") (pintype "passive"))
      (node (ref "Q12") (pin "2") (pinfunction "G_2") (pintype "passive"))
      (node (ref "R35") (pin "1") (pinfunction "1_1") (pintype "passive"))
      (node (ref "R36") (pin "2") (pinfunction "2_2") (pintype "passive"))
    )
    (net (code "76") (name "Net-(Q13-G)") (class "Default")
      (node (ref "C17") (pin "2") (pinfunction "2_2") (pintype "passive"))
      (node (ref "D13") (pin "A") (pinfunction "A_A") (pintype "passive"))
      (node (ref "Q13") (pin "2") (pinfunction "G_2") (pintype "passive"))
      (node (ref "R37") (pin "2") (pinfunction "2_2") (pintype "passive"))
      (node (ref "R38") (pin "2") (pinfunction "2_2") (pintype "passive"))
    )
    (net (code "77") (name "Net-(Q14-G)") (class "Default")
      (node (ref "C18") (pin "2") (pinfunction "2_2") (pintype "passive"))
      (node (ref "D14") (pin "A") (pinfunction "A_A") (pintype "passive"))
      (node (ref "Q14") (pin "2") (pinfunction "G_2") (pintype "passive"))
      (node (ref "R39") (pin "2") (pinfunction "2_2") (pintype "passive"))
      (node (ref "R40") (pin "2") (pinfunction "2_2") (pintype "passive"))
    )
    (net (code "78") (name "Net-(Q15-G)") (class "Default")
      (node (ref "C19") (pin "2") (pinfunction "2_2") (pintype "passive"))
      (node (ref "D15") (pin "A") (pinfunction "A_A") (pintype "passive"))
      (node (ref "Q15") (pin "2") (pinfunction "G_2") (pintype "passive"))
      (node (ref "R41") (pin "2") (pinfunction "2_2") (pintype "passive"))
      (node (ref "R42") (pin "2") (pinfunction "2_2") (pintype "passive"))
    )
    (net (code "79") (name "Net-(Q16-G)") (class "Default")
      (node (ref "C20") (pin "1") (pinfunction "1_1") (pintype "passive"))
      (node (ref "D16") (pin "C") (pinfunction "C_C") (pintype "passive"))
      (node (ref "Q16") (pin "2") (pinfunction "G_2") (pintype "passive"))
      (node (ref "R43") (pin "1") (pinfunction "1_1") (pintype "passive"))
      (node (ref "R44") (pin "2") (pinfunction "2_2") (pintype "passive"))
    )
    (net (code "80") (name "Net-(Q16-S)") (class "Default")
      (node (ref "C20") (pin "2") (pinfunction "2_2") (pintype "passive"))
      (node (ref "C21") (pin "2") (pinfunction "2_2") (pintype "passive"))
      (node (ref "C22") (pin "2") (pinfunction "2_2") (pintype "passive"))
      (node (ref "D16") (pin "A") (pinfunction "A_A") (pintype "passive"))
      (node (ref "D17") (pin "A") (pinfunction "A_A") (pintype "passive"))
      (node (ref "D18") (pin "A") (pinfunction "A_A") (pintype "passive"))
      (node (ref "Q16") (pin "1") (pinfunction "S_1") (pintype "passive"))
      (node (ref "Q17") (pin "1") (pinfunction "S_1") (pintype "passive"))
      (node (ref "Q18") (pin "1") (pinfunction "S_1") (pintype "passive"))
      (node (ref "R43") (pin "2") (pinfunction "2_2") (pintype "passive"))
      (node (ref "R45") (pin "2") (pinfunction "2_2") (pintype "passive"))
      (node (ref "R47") (pin "2") (pinfunction "2_2") (pintype "passive"))
      (node (ref "R64") (pin "1") (pinfunction "1_1") (pintype "passive"))
    )
    (net (code "81") (name "Net-(Q17-G)") (class "Default")
      (node (ref "C21") (pin "1") (pinfunction "1_1") (pintype "passive"))
      (node (ref "D17") (pin "C") (pinfunction "C_C") (pintype "passive"))
      (node (ref "Q17") (pin "2") (pinfunction "G_2") (pintype "passive"))
      (node (ref "R45") (pin "1") (pinfunction "1_1") (pintype "passive"))
      (node (ref "R46") (pin "2") (pinfunction "2_2") (pintype "passive"))
    )
    (net (code "82") (name "Net-(Q18-G)") (class "Default")
      (node (ref "C22") (pin "1") (pinfunction "1_1") (pintype "passive"))
      (node (ref "D18") (pin "C") (pinfunction "C_C") (pintype "passive"))
      (node (ref "Q18") (pin "2") (pinfunction "G_2") (pintype "passive"))
      (node (ref "R47") (pin "1") (pinfunction "1_1") (pintype "passive"))
      (node (ref "R48") (pin "2") (pinfunction "2_2") (pintype "passive"))
    )
    (net (code "83") (name "Net-(Q19-G)") (class "Default")
      (node (ref "C23") (pin "2") (pinfunction "2_2") (pintype "passive"))
      (node (ref "D19") (pin "A") (pinfunction "A_A") (pintype "passive"))
      (node (ref "Q19") (pin "2") (pinfunction "G_2") (pintype "passive"))
      (node (ref "R49") (pin "2") (pinfunction "2_2") (pintype "passive"))
      (node (ref "R50") (pin "2") (pinfunction "2_2") (pintype "passive"))
    )
    (net (code "84") (name "Net-(Q20-G)") (class "Default")
      (node (ref "C24") (pin "2") (pinfunction "2_2") (pintype "passive"))
      (node (ref "D20") (pin "A") (pinfunction "A_A") (pintype "passive"))
      (node (ref "Q20") (pin "2") (pinfunction "G_2") (pintype "passive"))
      (node (ref "R51") (pin "2") (pinfunction "2_2") (pintype "passive"))
      (node (ref "R52") (pin "2") (pinfunction "2_2") (pintype "passive"))
    )
    (net (code "85") (name "Net-(Q21-G)") (class "Default")
      (node (ref "C25") (pin "2") (pinfunction "2_2") (pintype "passive"))
      (node (ref "D21") (pin "A") (pinfunction "A_A") (pintype "passive"))
      (node (ref "Q21") (pin "2") (pinfunction "G_2") (pintype "passive"))
      (node (ref "R53") (pin "2") (pinfunction "2_2") (pintype "passive"))
      (node (ref "R54") (pin "2") (pinfunction "2_2") (pintype "passive"))
    )
    (net (code "86") (name "Net-(Q22-G)") (class "Default")
      (node (ref "C26") (pin "1") (pinfunction "1_1") (pintype "passive"))
      (node (ref "D22") (pin "C") (pinfunction "C_C") (pintype "passive"))
      (node (ref "Q22") (pin "2") (pinfunction "G_2") (pintype "passive"))
      (node (ref "R55") (pin "1") (pinfunction "1_1") (pintype "passive"))
      (node (ref "R56") (pin "2") (pinfunction "2_2") (pintype "passive"))
    )
    (net (code "87") (name "Net-(Q22-S)") (class "Default")
      (node (ref "C26") (pin "2") (pinfunction "2_2") (pintype "passive"))
      (node (ref "C27") (pin "2") (pinfunction "2_2") (pintype "passive"))
      (node (ref "C28") (pin "2") (pinfunction "2_2") (pintype "passive"))
      (node (ref "D22") (pin "A") (pinfunction "A_A") (pintype "passive"))
      (node (ref "D23") (pin "A") (pinfunction "A_A") (pintype "passive"))
      (node (ref "D24") (pin "A") (pinfunction "A_A") (pintype "passive"))
      (node (ref "Q22") (pin "1") (pinfunction "S_1") (pintype "passive"))
      (node (ref "Q23") (pin "1") (pinfunction "S_1") (pintype "passive"))
      (node (ref "Q24") (pin "1") (pinfunction "S_1") (pintype "passive"))
      (node (ref "R55") (pin "2") (pinfunction "2_2") (pintype "passive"))
      (node (ref "R57") (pin "2") (pinfunction "2_2") (pintype "passive"))
      (node (ref "R59") (pin "2") (pinfunction "2_2") (pintype "passive"))
      (node (ref "R61") (pin "1") (pinfunction "1_1") (pintype "passive"))
    )
    (net (code "88") (name "Net-(Q23-G)") (class "Default")
      (node (ref "C27") (pin "1") (pinfunction "1_1") (pintype "passive"))
      (node (ref "D23") (pin "C") (pinfunction "C_C") (pintype "passive"))
      (node (ref "Q23") (pin "2") (pinfunction "G_2") (pintype "passive"))
      (node (ref "R57") (pin "1") (pinfunction "1_1") (pintype "passive"))
      (node (ref "R58") (pin "2") (pinfunction "2_2") (pintype "passive"))
    )
    (net (code "89") (name "Net-(Q24-G)") (class "Default")
      (node (ref "C28") (pin "1") (pinfunction "1_1") (pintype "passive"))
      (node (ref "D24") (pin "C") (pinfunction "C_C") (pintype "passive"))
      (node (ref "Q24") (pin "2") (pinfunction "G_2") (pintype "passive"))
      (node (ref "R59") (pin "1") (pinfunction "1_1") (pintype "passive"))
      (node (ref "R60") (pin "2") (pinfunction "2_2") (pintype "passive"))
    )
    (net (code "90") (name "Net-(U1-PB3)") (class "Default")
      (node (ref "S6") (pin "1") (pinfunction "1_1") (pintype "passive"))
      (node (ref "SV3") (pin "1") (pinfunction "1_1") (pintype "passive"))
      (node (ref "U1") (pin "15") (pinfunction "PB3_15") (pintype "bidirectional"))
    )
    (net (code "91") (name "Net-(U1-PB4)") (class "Default")
      (node (ref "S7") (pin "1") (pinfunction "1_1") (pintype "passive"))
      (node (ref "SV3") (pin "2") (pinfunction "2_2") (pintype "passive"))
      (node (ref "U1") (pin "16") (pinfunction "PB4_16") (pintype "bidirectional"))
    )
    (net (code "92") (name "Net-(U1-PB5)") (class "Default")
      (node (ref "S8") (pin "2") (pinfunction "2_2") (pintype "passive"))
      (node (ref "U1") (pin "17") (pinfunction "PB5_17") (pintype "bidirectional"))
    )
    (net (code "93") (name "Net-(U1-PB6)") (class "Default")
      (node (ref "C29") (pin "2") (pinfunction "2_2") (pintype "passive"))
      (node (ref "Q26") (pin "1") (pinfunction "1_1") (pintype "passive"))
      (node (ref "U1") (pin "7") (pinfunction "PB6_7") (pintype "bidirectional"))
    )
    (net (code "94") (name "Net-(U1-PB7)") (class "Default")
      (node (ref "C30") (pin "2") (pinfunction "2_2") (pintype "passive"))
      (node (ref "Q26") (pin "2") (pinfunction "2_2") (pintype "passive"))
      (node (ref "U1") (pin "8") (pinfunction "PB7_8") (pintype "bidirectional"))
    )
    (net (code "95") (name "Net-(U1-PC6{slash}~{RESET})") (class "Default")
      (node (ref "SV3") (pin "4") (pinfunction "4_4") (pintype "passive"))
      (node (ref "U1") (pin "29") (pinfunction "PC6/~{RESET}_29") (pintype "bidirectional"))
    )
    (net (code "96") (name "Net-(U1-PD0)") (class "Default")
      (node (ref "R11") (pin "1") (pinfunction "1_1") (pintype "passive"))
      (node (ref "U1") (pin "30") (pinfunction "PD0_30") (pintype "bidirectional"))
    )
    (net (code "97") (name "Net-(U1-PD1)") (class "Default")
      (node (ref "R5") (pin "1") (pinfunction "1_1") (pintype "passive"))
      (node (ref "U1") (pin "31") (pinfunction "PD1_31") (pintype "bidirectional"))
    )
    (net (code "98") (name "Net-(U1-PD2)") (class "Default")
      (node (ref "R9") (pin "2") (pinfunction "2_2") (pintype "passive"))
      (node (ref "U1") (pin "32") (pinfunction "PD2_32") (pintype "bidirectional"))
    )
    (net (code "99") (name "Net-(U1-PD4)") (class "Default")
      (node (ref "R7") (pin "1") (pinfunction "1_1") (pintype "passive"))
      (node (ref "U1") (pin "2") (pinfunction "PD4_2") (pintype "bidirectional"))
    )
    (net (code "100") (name "Net-(U2-PB3)") (class "Default")
      (node (ref "S3") (pin "2") (pinfunction "2_2") (pintype "passive"))
      (node (ref "SV4") (pin "3") (pinfunction "3_3") (pintype "passive"))
      (node (ref "U2") (pin "15") (pinfunction "PB3_15") (pintype "bidirectional"))
    )
    (net (code "101") (name "Net-(U2-PB4)") (class "Default")
      (node (ref "S4") (pin "2") (pinfunction "2_2") (pintype "passive"))
      (node (ref "SV4") (pin "2") (pinfunction "2_2") (pintype "passive"))
      (node (ref "U2") (pin "16") (pinfunction "PB4_16") (pintype "bidirectional"))
    )
    (net (code "102") (name "Net-(U2-PB5)") (class "Default")
      (node (ref "S5") (pin "1") (pinfunction "1_1") (pintype "passive"))
      (node (ref "SV4") (pin "1") (pinfunction "1_1") (pintype "passive"))
      (node (ref "U2") (pin "17") (pinfunction "PB5_17") (pintype "bidirectional"))
    )
    (net (code "103") (name "Net-(U2-PB6)") (class "Default")
      (node (ref "C31") (pin "2") (pinfunction "2_2") (pintype "passive"))
      (node (ref "Q25") (pin "2") (pinfunction "2_2") (pintype "passive"))
      (node (ref "U2") (pin "7") (pinfunction "PB6_7") (pintype "bidirectional"))
    )
    (net (code "104") (name "Net-(U2-PB7)") (class "Default")
      (node (ref "C32") (pin "2") (pinfunction "2_2") (pintype "passive"))
      (node (ref "Q25") (pin "1") (pinfunction "1_1") (pintype "passive"))
      (node (ref "U2") (pin "8") (pinfunction "PB7_8") (pintype "bidirectional"))
    )
    (net (code "105") (name "Net-(U2-PC6{slash}~{RESET})") (class "Default")
      (node (ref "SV4") (pin "4") (pinfunction "4_4") (pintype "passive"))
      (node (ref "U2") (pin "29") (pinfunction "PC6/~{RESET}_29") (pintype "bidirectional"))
    )
    (net (code "106") (name "Net-(U3-QB)") (class "Default")
      (node (ref "S5") (pin "2") (pinfunction "2_2") (pintype "passive"))
      (node (ref "U3") (pin "1") (pinfunction "QB_1") (pintype "output"))
    )
    (net (code "107") (name "Net-(U3-QC)") (class "Default")
      (node (ref "S8") (pin "1") (pinfunction "1_1") (pintype "passive"))
      (node (ref "SV3") (pin "3") (pinfunction "3_3") (pintype "passive"))
      (node (ref "U3") (pin "2") (pinfunction "QC_2") (pintype "output"))
    )
    (net (code "108") (name "Net-(U3-QD)") (class "Default")
      (node (ref "U3") (pin "3") (pinfunction "QD_3") (pintype "output"))
      (node (ref "U4") (pin "12") (pinfunction "SCK_12") (pintype "input"))
    )
    (net (code "109") (name "Net-(U5-ADJUST)") (class "Default")
      (node (ref "R1") (pin "2") (pinfunction "2_2") (pintype "passive"))
      (node (ref "R2") (pin "1") (pinfunction "1_1") (pintype "passive"))
      (node (ref "U5") (pin "2") (pinfunction "ADJUST_2") (pintype "passive"))
    )
    (net (code "110") (name "Net-(U5-IN)") (class "Default")
      (node (ref "C1") (pin "1") (pinfunction "1_1") (pintype "passive"))
      (node (ref "S1") (pin "2") (pinfunction "2_2") (pintype "passive"))
      (node (ref "U5") (pin "1") (pinfunction "IN_1") (pintype "input"))
    )
    (net (code "111") (name "Net-(U6-ADJUST)") (class "Default")
      (node (ref "R3") (pin "2") (pinfunction "2_2") (pintype "passive"))
      (node (ref "R4") (pin "1") (pinfunction "1_1") (pintype "passive"))
      (node (ref "U6") (pin "2") (pinfunction "ADJUST_2") (pintype "passive"))
    )
    (net (code "112") (name "Net-(U6-IN)") (class "Default")
      (node (ref "C3") (pin "1") (pinfunction "1_1") (pintype "passive"))
      (node (ref "S2") (pin "2") (pinfunction "2_2") (pintype "passive"))
      (node (ref "U6") (pin "1") (pinfunction "IN_1") (pintype "input"))
    )
    (net (code "113") (name "unconnected-(IC1-+3.3V_1-Pad1)") (class "Default")
      (node (ref "IC1") (pin "1") (pinfunction "+3.3V_1_1") (pintype "bidirectional"))
    )
    (net (code "114") (name "unconnected-(IC1-+3.3V_2-Pad17)") (class "Default")
      (node (ref "IC1") (pin "17") (pinfunction "+3.3V_2_17") (pintype "bidirectional"))
    )
    (net (code "115") (name "unconnected-(IC1-+5V_2-Pad4)") (class "Default")
      (node (ref "IC1") (pin "4") (pinfunction "+5V_2_4") (pintype "bidirectional"))
    )
    (net (code "116") (name "unconnected-(IC1-DNC_1-Pad27)") (class "Default")
      (node (ref "IC1") (pin "27") (pinfunction "DNC_1_27") (pintype "bidirectional"))
    )
    (net (code "117") (name "unconnected-(IC1-DNC_2-Pad28)") (class "Default")
      (node (ref "IC1") (pin "28") (pinfunction "DNC_2_28") (pintype "bidirectional"))
    )
    (net (code "118") (name "unconnected-(IC1-GND_2-Pad9)") (class "Default")
      (node (ref "IC1") (pin "9") (pinfunction "GND_2_9") (pintype "bidirectional"))
    )
    (net (code "119") (name "unconnected-(IC1-GND_3-Pad14)") (class "Default")
      (node (ref "IC1") (pin "14") (pinfunction "GND_3_14") (pintype "bidirectional"))
    )
    (net (code "120") (name "unconnected-(IC1-GND_4-Pad20)") (class "Default")
      (node (ref "IC1") (pin "20") (pinfunction "GND_4_20") (pintype "bidirectional"))
    )
    (net (code "121") (name "unconnected-(IC1-GND_5-Pad25)") (class "Default")
      (node (ref "IC1") (pin "25") (pinfunction "GND_5_25") (pintype "bidirectional"))
    )
    (net (code "122") (name "unconnected-(IC1-GND_6-Pad30)") (class "Default")
      (node (ref "IC1") (pin "30") (pinfunction "GND_6_30") (pintype "bidirectional"))
    )
    (net (code "123") (name "unconnected-(IC1-GND_7-Pad34)") (class "Default")
      (node (ref "IC1") (pin "34") (pinfunction "GND_7_34") (pintype "bidirectional"))
    )
    (net (code "124") (name "unconnected-(IC1-GND_8-Pad39)") (class "Default")
      (node (ref "IC1") (pin "39") (pinfunction "GND_8_39") (pintype "bidirectional"))
    )
    (net (code "125") (name "unconnected-(IC1-GPIO5{slash}{slash}GPCLK1-Pad29)") (class "Default")
      (node (ref "IC1") (pin "29") (pinfunction "GPIO5//GPCLK1_29") (pintype "bidirectional"))
    )
    (net (code "126") (name "unconnected-(IC1-GPIO6{slash}GPCLK2-Pad31)") (class "Default")
      (node (ref "IC1") (pin "31") (pinfunction "GPIO6/GPCLK2_31") (pintype "bidirectional"))
    )
    (net (code "127") (name "unconnected-(IC1-GPIO12{slash}PWM0-Pad32)") (class "Default")
      (node (ref "IC1") (pin "32") (pinfunction "GPIO12/PWM0_32") (pintype "bidirectional"))
    )
    (net (code "128") (name "unconnected-(IC1-GPIO13{slash}PWM1-Pad33)") (class "Default")
      (node (ref "IC1") (pin "33") (pinfunction "GPIO13/PWM1_33") (pintype "bidirectional"))
    )
    (net (code "129") (name "unconnected-(IC1-GPIO16{slash}SPI1_CS2-Pad36)") (class "Default")
      (node (ref "IC1") (pin "36") (pinfunction "GPIO16/SPI1_CS2_36") (pintype "bidirectional"))
    )
    (net (code "130") (name "unconnected-(IC1-GPIO19{slash}SPI0_MISO1{slash}PWM1-Pad35)") (class "Default")
      (node (ref "IC1") (pin "35") (pinfunction "GPIO19/SPI0_MISO1/PWM1_35") (pintype "bidirectional"))
    )
    (net (code "131") (name "unconnected-(IC1-GPIO20{slash}SPI0_MOSI1-Pad38)") (class "Default")
      (node (ref "IC1") (pin "38") (pinfunction "GPIO20/SPI0_MOSI1_38") (pintype "bidirectional"))
    )
    (net (code "132") (name "unconnected-(IC1-GPIO21{slash}SPI0_SCLK1-Pad40)") (class "Default")
      (node (ref "IC1") (pin "40") (pinfunction "GPIO21/SPI0_SCLK1_40") (pintype "bidirectional"))
    )
    (net (code "133") (name "unconnected-(IC1-GPIO26-Pad37)") (class "Default")
      (node (ref "IC1") (pin "37") (pinfunction "GPIO26_37") (pintype "bidirectional"))
    )
    (net (code "134") (name "unconnected-(IC1-GPIO27-Pad13)") (class "Default")
      (node (ref "IC1") (pin "13") (pinfunction "GPIO27_13") (pintype "bidirectional"))
    )
    (net (code "135") (name "unconnected-(IC1-GPIO_2{slash}[I2C]_SDA-Pad3)") (class "Default")
      (node (ref "IC1") (pin "3") (pinfunction "GPIO_2/[I2C]_SDA_3") (pintype "bidirectional"))
    )
    (net (code "136") (name "unconnected-(IC1-GPIO_3{slash}[I2C]_SCL-Pad5)") (class "Default")
      (node (ref "IC1") (pin "5") (pinfunction "GPIO_3/[I2C]_SCL_5") (pintype "bidirectional"))
    )
    (net (code "137") (name "unconnected-(IC1-GPIO_4{slash}GPCLK0-Pad7)") (class "Default")
      (node (ref "IC1") (pin "7") (pinfunction "GPIO_4/GPCLK0_7") (pintype "bidirectional"))
    )
    (net (code "138") (name "unconnected-(IC1-GPIO_14{slash}[UART]_TXD0-Pad8)") (class "Default")
      (node (ref "IC1") (pin "8") (pinfunction "GPIO_14/[UART]_TXD0_8") (pintype "bidirectional"))
    )
    (net (code "139") (name "unconnected-(IC1-GPIO_15{slash}[UART]_RXD0-Pad10)") (class "Default")
      (node (ref "IC1") (pin "10") (pinfunction "GPIO_15/[UART]_RXD0_10") (pintype "bidirectional"))
    )
    (net (code "140") (name "unconnected-(IC1-GPIO_18{slash}PWM0{slash}SPI1_CS0-Pad12)") (class "Default")
      (node (ref "IC1") (pin "12") (pinfunction "GPIO_18/PWM0/SPI1_CS0_12") (pintype "bidirectional"))
    )
    (net (code "141") (name "unconnected-(IC1-GPIO_22-Pad15)") (class "Default")
      (node (ref "IC1") (pin "15") (pinfunction "GPIO_22_15") (pintype "bidirectional"))
    )
    (net (code "142") (name "unconnected-(IC1-GPIO_23-Pad16)") (class "Default")
      (node (ref "IC1") (pin "16") (pinfunction "GPIO_23_16") (pintype "bidirectional"))
    )
    (net (code "143") (name "unconnected-(IC1-GPIO_24-Pad18)") (class "Default")
      (node (ref "IC1") (pin "18") (pinfunction "GPIO_24_18") (pintype "bidirectional"))
    )
    (net (code "144") (name "unconnected-(IC1-RUN_1-Pad41)") (class "Default")
      (node (ref "IC1") (pin "41") (pinfunction "RUN_1_41") (pintype "bidirectional"))
    )
    (net (code "145") (name "unconnected-(IC1-RUN_2-Pad42)") (class "Default")
      (node (ref "IC1") (pin "42") (pinfunction "RUN_2_42") (pintype "bidirectional"))
    )
    (net (code "146") (name "unconnected-(IC1-TV_+-Pad43)") (class "Default")
      (node (ref "IC1") (pin "43") (pinfunction "TV_+_43") (pintype "bidirectional"))
    )
    (net (code "147") (name "unconnected-(IC1-TV_--Pad44)") (class "Default")
      (node (ref "IC1") (pin "44") (pinfunction "TV_-_44") (pintype "bidirectional"))
    )
    (net (code "148") (name "unconnected-(IC2-DIS-Pad4)") (class "Default")
      (node (ref "IC2") (pin "4") (pinfunction "DIS_4") (pintype "bidirectional"))
    )
    (net (code "149") (name "unconnected-(IC2-OCDET-Pad21)") (class "Default")
      (node (ref "IC2") (pin "21") (pinfunction "OCDET_21") (pintype "bidirectional"))
    )
    (net (code "150") (name "unconnected-(IC2-OUTFG-Pad8)") (class "Default")
      (node (ref "IC2") (pin "8") (pinfunction "OUTFG_8") (pintype "bidirectional"))
    )
    (net (code "151") (name "unconnected-(IC2-TEST-Pad2)") (class "Default")
      (node (ref "IC2") (pin "2") (pinfunction "TEST_2") (pintype "bidirectional"))
    )
    (net (code "152") (name "unconnected-(IC2-WAVE_CMP-Pad20)") (class "Default")
      (node (ref "IC2") (pin "20") (pinfunction "WAVE_CMP_20") (pintype "bidirectional"))
    )
    (net (code "153") (name "unconnected-(IC3-DIS-Pad4)") (class "Default")
      (node (ref "IC3") (pin "4") (pinfunction "DIS_4") (pintype "bidirectional"))
    )
    (net (code "154") (name "unconnected-(IC3-OCDET-Pad21)") (class "Default")
      (node (ref "IC3") (pin "21") (pinfunction "OCDET_21") (pintype "bidirectional"))
    )
    (net (code "155") (name "unconnected-(IC3-OUTFG-Pad8)") (class "Default")
      (node (ref "IC3") (pin "8") (pinfunction "OUTFG_8") (pintype "bidirectional"))
    )
    (net (code "156") (name "unconnected-(IC3-TEST-Pad2)") (class "Default")
      (node (ref "IC3") (pin "2") (pinfunction "TEST_2") (pintype "bidirectional"))
    )
    (net (code "157") (name "unconnected-(IC3-WAVE_CMP-Pad20)") (class "Default")
      (node (ref "IC3") (pin "20") (pinfunction "WAVE_CMP_20") (pintype "bidirectional"))
    )
    (net (code "158") (name "unconnected-(IC4-DIS-Pad4)") (class "Default")
      (node (ref "IC4") (pin "4") (pinfunction "DIS_4") (pintype "bidirectional"))
    )
    (net (code "159") (name "unconnected-(IC4-OCDET-Pad21)") (class "Default")
      (node (ref "IC4") (pin "21") (pinfunction "OCDET_21") (pintype "bidirectional"))
    )
    (net (code "160") (name "unconnected-(IC4-OUTFG-Pad8)") (class "Default")
      (node (ref "IC4") (pin "8") (pinfunction "OUTFG_8") (pintype "bidirectional"))
    )
    (net (code "161") (name "unconnected-(IC4-TEST-Pad2)") (class "Default")
      (node (ref "IC4") (pin "2") (pinfunction "TEST_2") (pintype "bidirectional"))
    )
    (net (code "162") (name "unconnected-(IC4-WAVE_CMP-Pad20)") (class "Default")
      (node (ref "IC4") (pin "20") (pinfunction "WAVE_CMP_20") (pintype "bidirectional"))
    )
    (net (code "163") (name "unconnected-(IC5-DIS-Pad4)") (class "Default")
      (node (ref "IC5") (pin "4") (pinfunction "DIS_4") (pintype "bidirectional"))
    )
    (net (code "164") (name "unconnected-(IC5-OCDET-Pad21)") (class "Default")
      (node (ref "IC5") (pin "21") (pinfunction "OCDET_21") (pintype "bidirectional"))
    )
    (net (code "165") (name "unconnected-(IC5-OUTFG-Pad8)") (class "Default")
      (node (ref "IC5") (pin "8") (pinfunction "OUTFG_8") (pintype "bidirectional"))
    )
    (net (code "166") (name "unconnected-(IC5-TEST-Pad2)") (class "Default")
      (node (ref "IC5") (pin "2") (pinfunction "TEST_2") (pintype "bidirectional"))
    )
    (net (code "167") (name "unconnected-(IC5-WAVE_CMP-Pad20)") (class "Default")
      (node (ref "IC5") (pin "20") (pinfunction "WAVE_CMP_20") (pintype "bidirectional"))
    )
    (net (code "168") (name "unconnected-(JP2-Pad5)") (class "Default")
      (node (ref "JP2") (pin "5") (pinfunction "5_5") (pintype "passive"))
    )
    (net (code "169") (name "unconnected-(JP2-Pad6)") (class "Default")
      (node (ref "JP2") (pin "6") (pinfunction "6_6") (pintype "passive"))
    )
    (net (code "170") (name "unconnected-(JP2-Pad7)") (class "Default")
      (node (ref "JP2") (pin "7") (pinfunction "7_7") (pintype "passive"))
    )
    (net (code "171") (name "unconnected-(JP2-Pad8)") (class "Default")
      (node (ref "JP2") (pin "8") (pinfunction "8_8") (pintype "passive"))
    )
    (net (code "172") (name "unconnected-(U1-ADC6-Pad19)") (class "Default")
      (node (ref "U1") (pin "19") (pinfunction "ADC6_19") (pintype "bidirectional"))
    )
    (net (code "173") (name "unconnected-(U1-ADC7-Pad22)") (class "Default")
      (node (ref "U1") (pin "22") (pinfunction "ADC7_22") (pintype "bidirectional"))
    )
    (net (code "174") (name "unconnected-(U1-AREF-Pad20)") (class "Default")
      (node (ref "U1") (pin "20") (pinfunction "AREF_20") (pintype "input"))
    )
    (net (code "175") (name "unconnected-(U1-PC0-Pad23)") (class "Default")
      (node (ref "U1") (pin "23") (pinfunction "PC0_23") (pintype "bidirectional"))
    )
    (net (code "176") (name "unconnected-(U1-PC1-Pad24)") (class "Default")
      (node (ref "U1") (pin "24") (pinfunction "PC1_24") (pintype "bidirectional"))
    )
    (net (code "177") (name "unconnected-(U1-PC2-Pad25)") (class "Default")
      (node (ref "U1") (pin "25") (pinfunction "PC2_25") (pintype "bidirectional"))
    )
    (net (code "178") (name "unconnected-(U1-PC3-Pad26)") (class "Default")
      (node (ref "U1") (pin "26") (pinfunction "PC3_26") (pintype "bidirectional"))
    )
    (net (code "179") (name "unconnected-(U1-PC4-Pad27)") (class "Default")
      (node (ref "U1") (pin "27") (pinfunction "PC4_27") (pintype "bidirectional"))
    )
    (net (code "180") (name "unconnected-(U1-PC5-Pad28)") (class "Default")
      (node (ref "U1") (pin "28") (pinfunction "PC5_28") (pintype "bidirectional"))
    )
    (net (code "181") (name "unconnected-(U2-ADC6-Pad19)") (class "Default")
      (node (ref "U2") (pin "19") (pinfunction "ADC6_19") (pintype "bidirectional"))
    )
    (net (code "182") (name "unconnected-(U2-ADC7-Pad22)") (class "Default")
      (node (ref "U2") (pin "22") (pinfunction "ADC7_22") (pintype "bidirectional"))
    )
    (net (code "183") (name "unconnected-(U2-AREF-Pad20)") (class "Default")
      (node (ref "U2") (pin "20") (pinfunction "AREF_20") (pintype "input"))
    )
    (net (code "184") (name "unconnected-(U2-PB0-Pad12)") (class "Default")
      (node (ref "U2") (pin "12") (pinfunction "PB0_12") (pintype "bidirectional"))
    )
    (net (code "185") (name "unconnected-(U2-PB1-Pad13)") (class "Default")
      (node (ref "U2") (pin "13") (pinfunction "PB1_13") (pintype "bidirectional"))
    )
    (net (code "186") (name "unconnected-(U2-PC0-Pad23)") (class "Default")
      (node (ref "U2") (pin "23") (pinfunction "PC0_23") (pintype "bidirectional"))
    )
    (net (code "187") (name "unconnected-(U2-PC1-Pad24)") (class "Default")
      (node (ref "U2") (pin "24") (pinfunction "PC1_24") (pintype "bidirectional"))
    )
    (net (code "188") (name "unconnected-(U2-PC2-Pad25)") (class "Default")
      (node (ref "U2") (pin "25") (pinfunction "PC2_25") (pintype "bidirectional"))
    )
    (net (code "189") (name "unconnected-(U2-PC3-Pad26)") (class "Default")
      (node (ref "U2") (pin "26") (pinfunction "PC3_26") (pintype "bidirectional"))
    )
    (net (code "190") (name "unconnected-(U2-PD2-Pad32)") (class "Default")
      (node (ref "U2") (pin "32") (pinfunction "PD2_32") (pintype "bidirectional"))
    )
    (net (code "191") (name "unconnected-(U2-PD3-Pad1)") (class "Default")
      (node (ref "U2") (pin "1") (pinfunction "PD3_1") (pintype "bidirectional"))
    )
    (net (code "192") (name "unconnected-(U2-PD4-Pad2)") (class "Default")
      (node (ref "U2") (pin "2") (pinfunction "PD4_2") (pintype "bidirectional"))
    )
    (net (code "193") (name "unconnected-(U2-PD5-Pad9)") (class "Default")
      (node (ref "U2") (pin "9") (pinfunction "PD5_9") (pintype "bidirectional"))
    )
    (net (code "194") (name "unconnected-(U2-PD6-Pad10)") (class "Default")
      (node (ref "U2") (pin "10") (pinfunction "PD6_10") (pintype "bidirectional"))
    )
    (net (code "195") (name "unconnected-(U2-PD7-Pad11)") (class "Default")
      (node (ref "U2") (pin "11") (pinfunction "PD7_11") (pintype "bidirectional"))
    )
    (net (code "196") (name "unconnected-(U3-QA-Pad15)") (class "Default")
      (node (ref "U3") (pin "15") (pinfunction "QA_15") (pintype "output"))
    )
    (net (code "197") (name "unconnected-(U3-QE-Pad4)") (class "Default")
      (node (ref "U3") (pin "4") (pinfunction "QE_4") (pintype "output"))
    )
    (net (code "198") (name "unconnected-(U3-QF-Pad5)") (class "Default")
      (node (ref "U3") (pin "5") (pinfunction "QF_5") (pintype "output"))
    )
    (net (code "199") (name "unconnected-(U3-QG-Pad6)") (class "Default")
      (node (ref "U3") (pin "6") (pinfunction "QG_6") (pintype "output"))
    )
    (net (code "200") (name "unconnected-(U3-QH'-Pad9)") (class "Default")
      (node (ref "U3") (pin "9") (pinfunction "QH'_9") (pintype "output"))
    )
    (net (code "201") (name "unconnected-(U3-QH-Pad7)") (class "Default")
      (node (ref "U3") (pin "7") (pinfunction "QH_7") (pintype "output"))
    )
    (net (code "202") (name "unconnected-(U4-DI00-Pad5)") (class "Default")
      (node (ref "U4") (pin "5") (pinfunction "DI00_5") (pintype "bidirectional"))
    )
    (net (code "203") (name "unconnected-(U4-DI01-Pad6)") (class "Default")
      (node (ref "U4") (pin "6") (pinfunction "DI01_6") (pintype "bidirectional"))
    )
    (net (code "204") (name "unconnected-(U4-DI02-Pad7)") (class "Default")
      (node (ref "U4") (pin "7") (pinfunction "DI02_7") (pintype "bidirectional"))
    )
    (net (code "205") (name "unconnected-(U4-DI03-Pad8)") (class "Default")
      (node (ref "U4") (pin "8") (pinfunction "DI03_8") (pintype "bidirectional"))
    )
    (net (code "206") (name "unconnected-(U4-DI04-Pad10)") (class "Default")
      (node (ref "U4") (pin "10") (pinfunction "DI04_10") (pintype "bidirectional"))
    )
    (net (code "207") (name "unconnected-(U4-DI05-Pad11)") (class "Default")
      (node (ref "U4") (pin "11") (pinfunction "DI05_11") (pintype "bidirectional"))
    )
  )
)
